# UFBmod_1V0.net
KiCad netlist of a schematic drawn in EAGLE
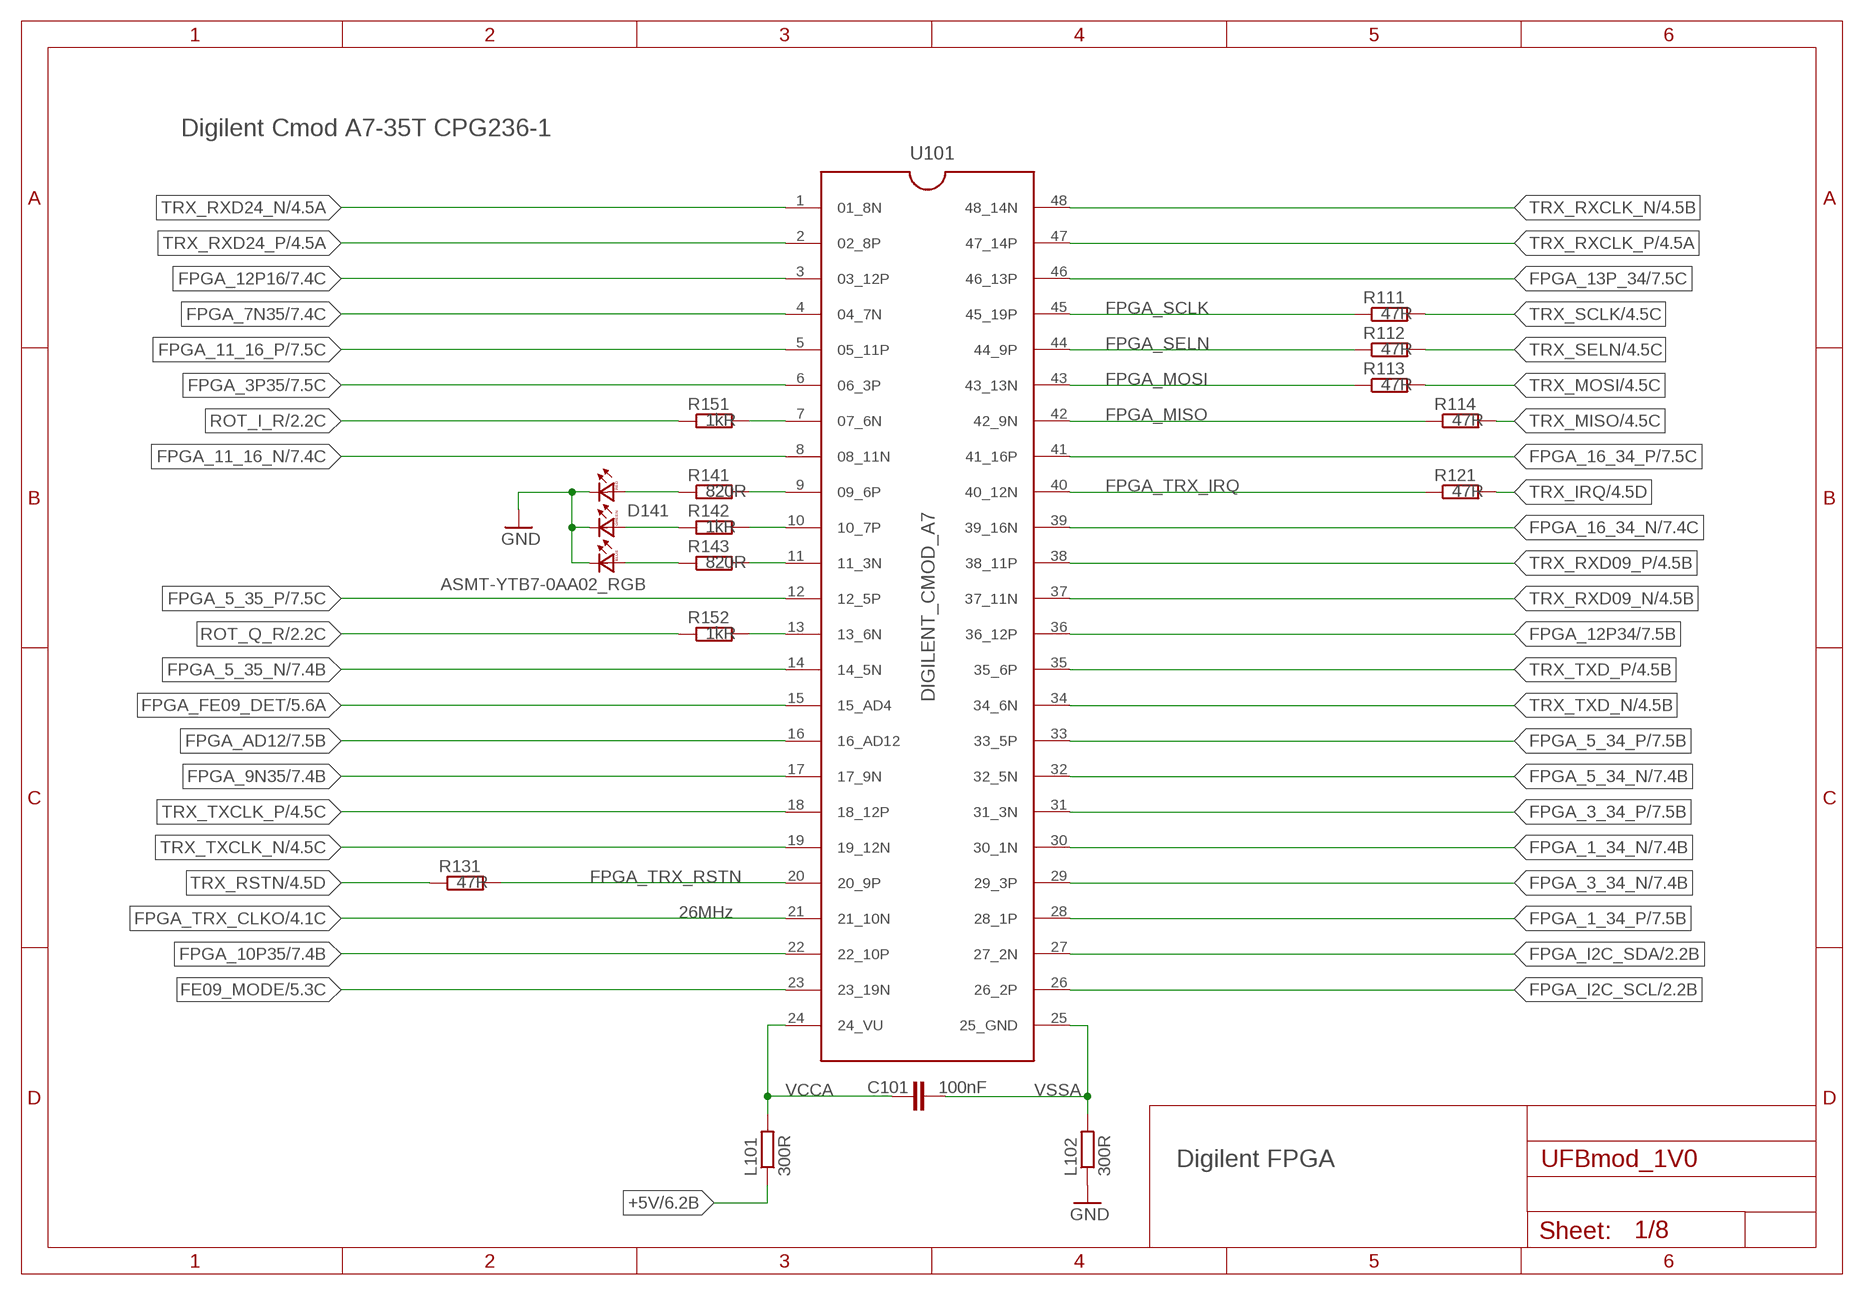
[diagram p0: schematic, sheet 1]
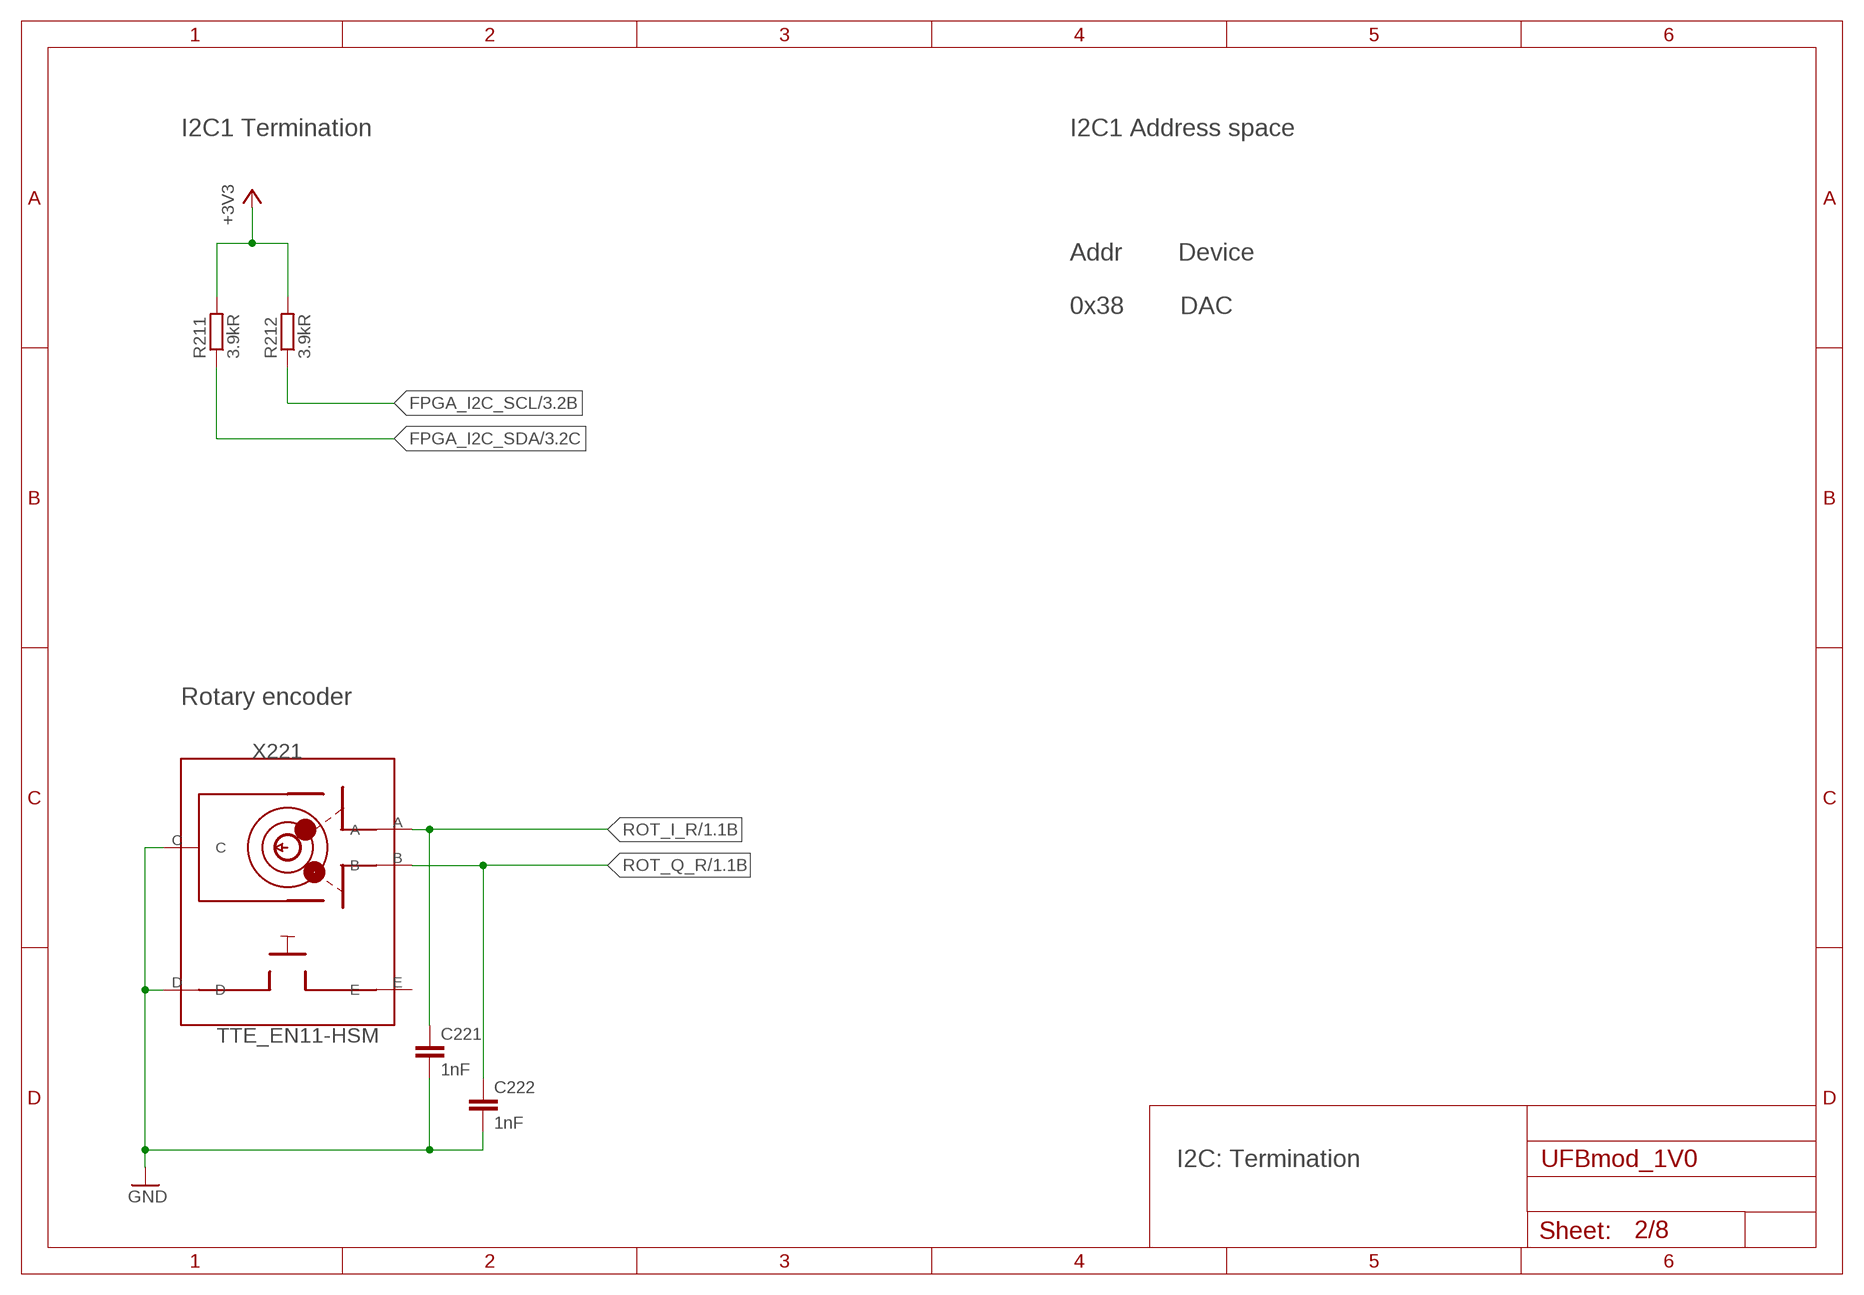
[diagram p1: schematic, sheet 2]
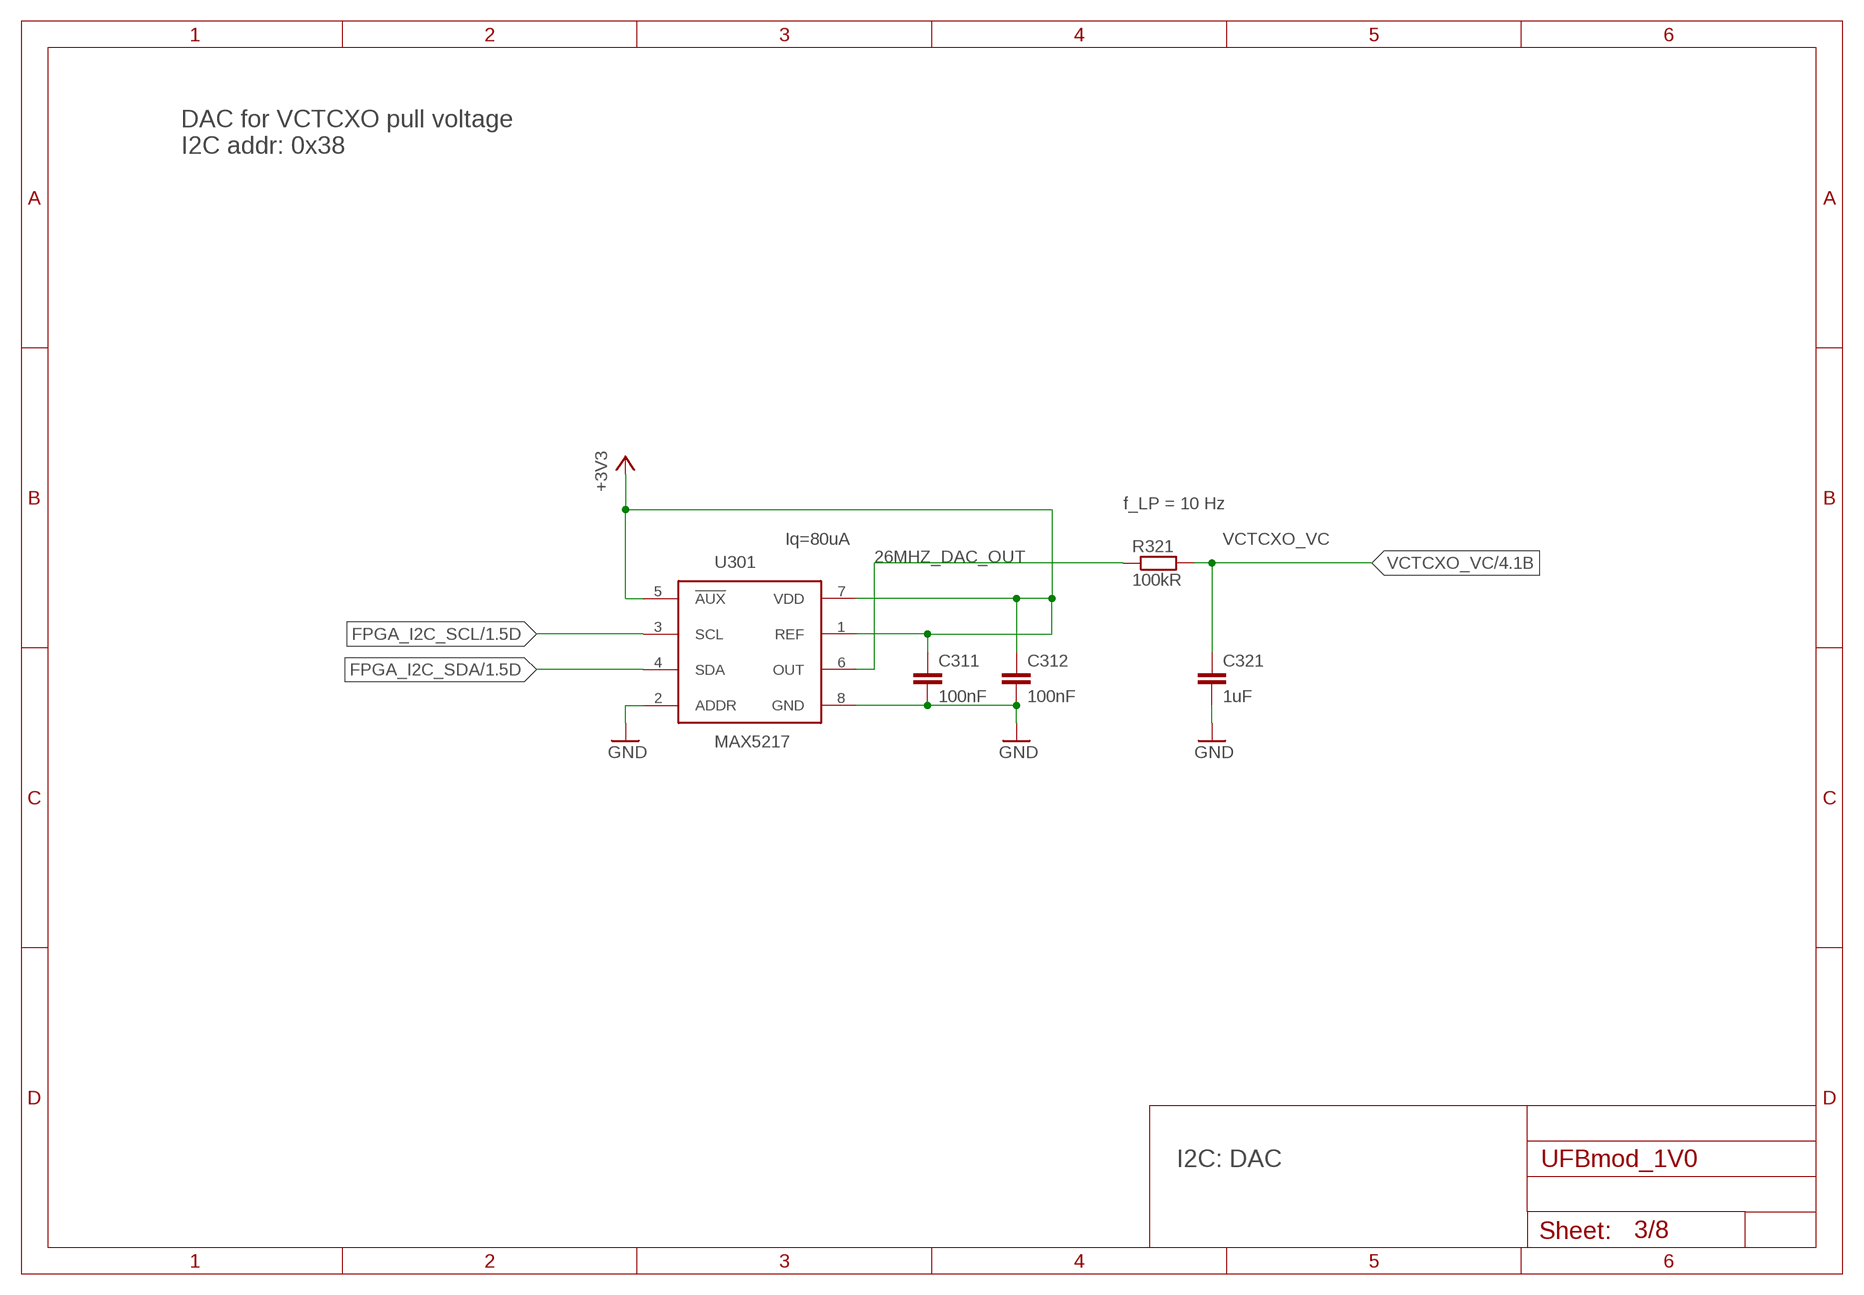
[diagram p2: schematic, sheet 3]
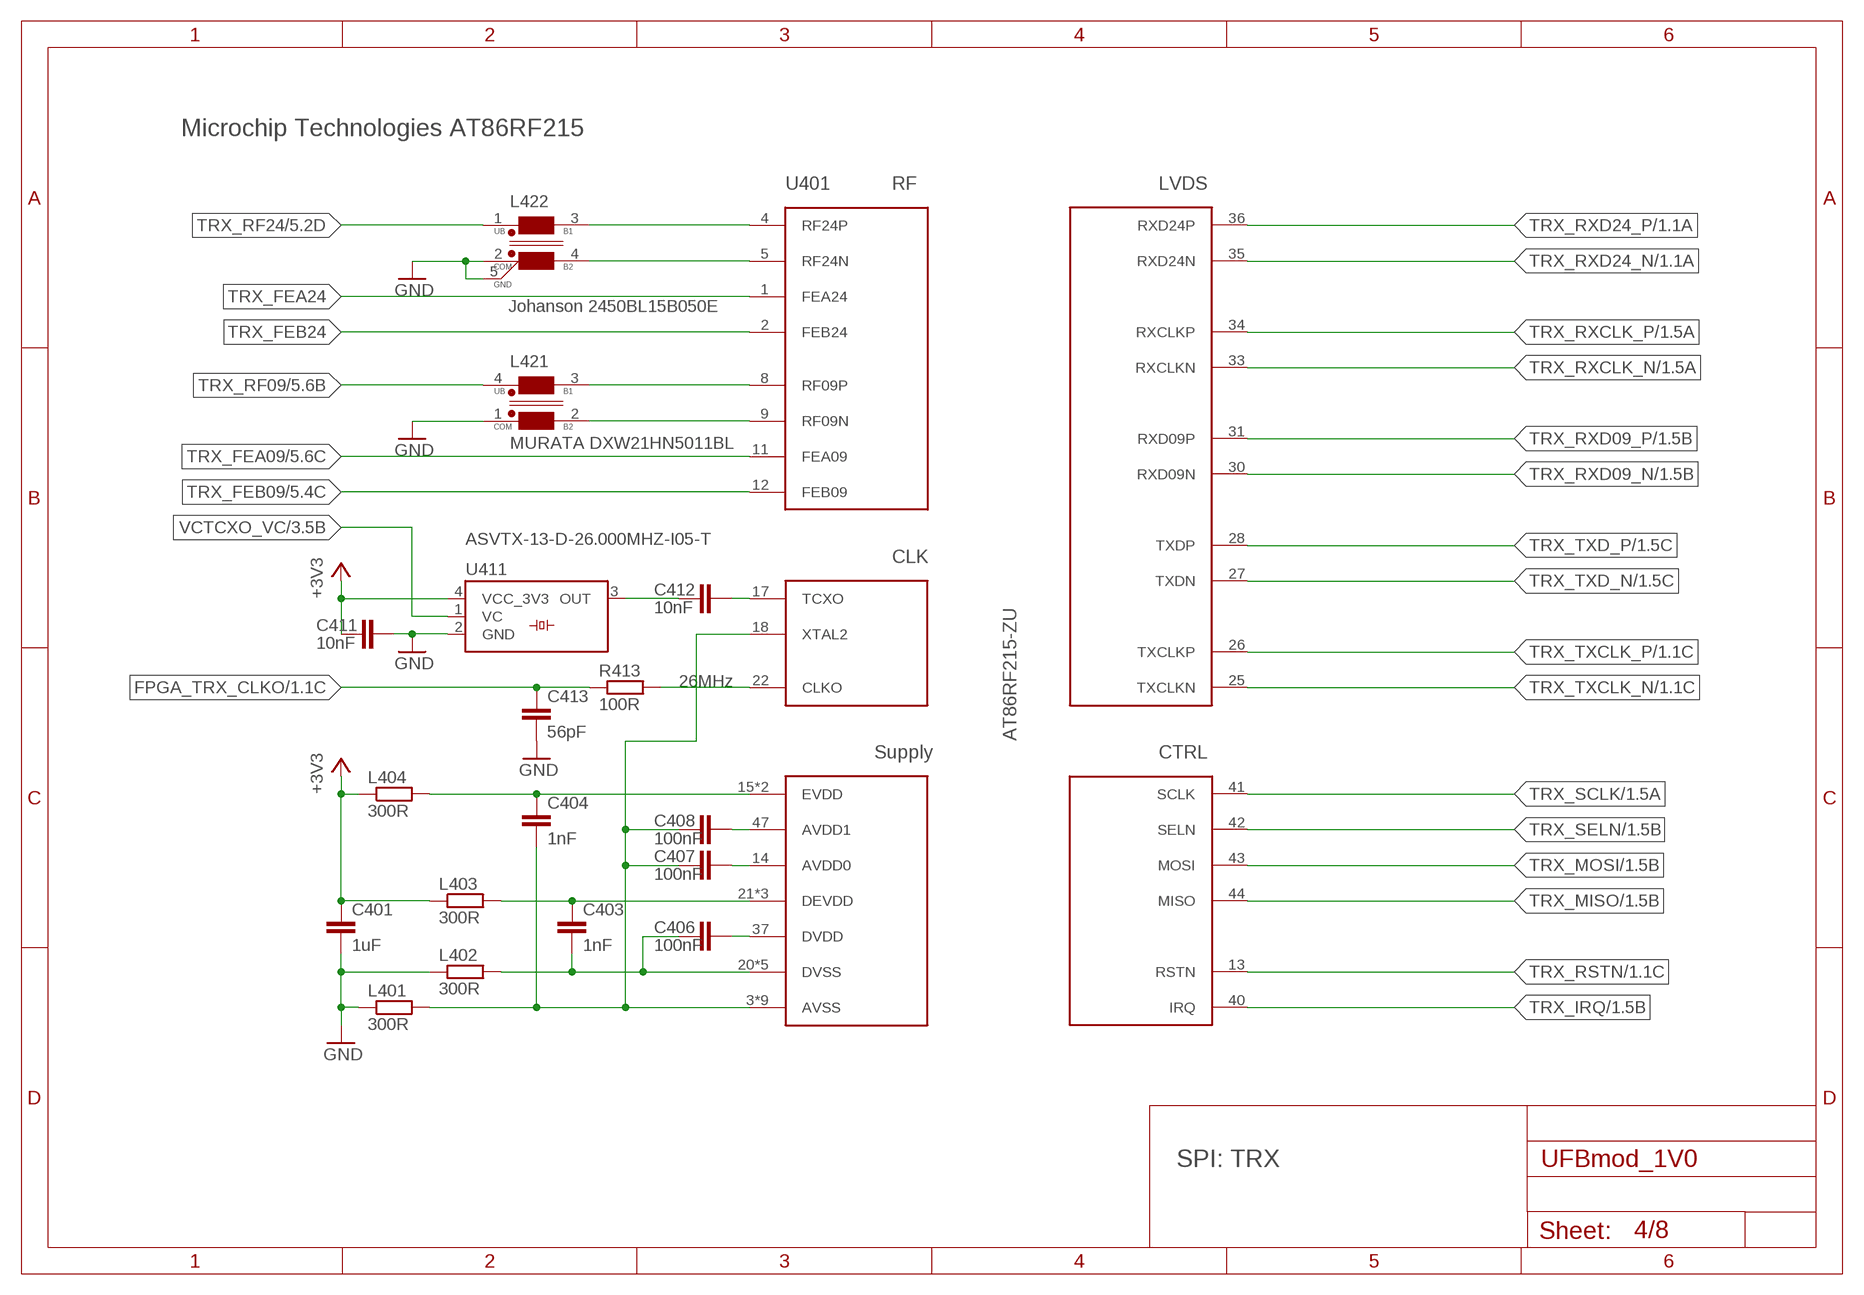
[diagram p3: schematic, sheet 4]
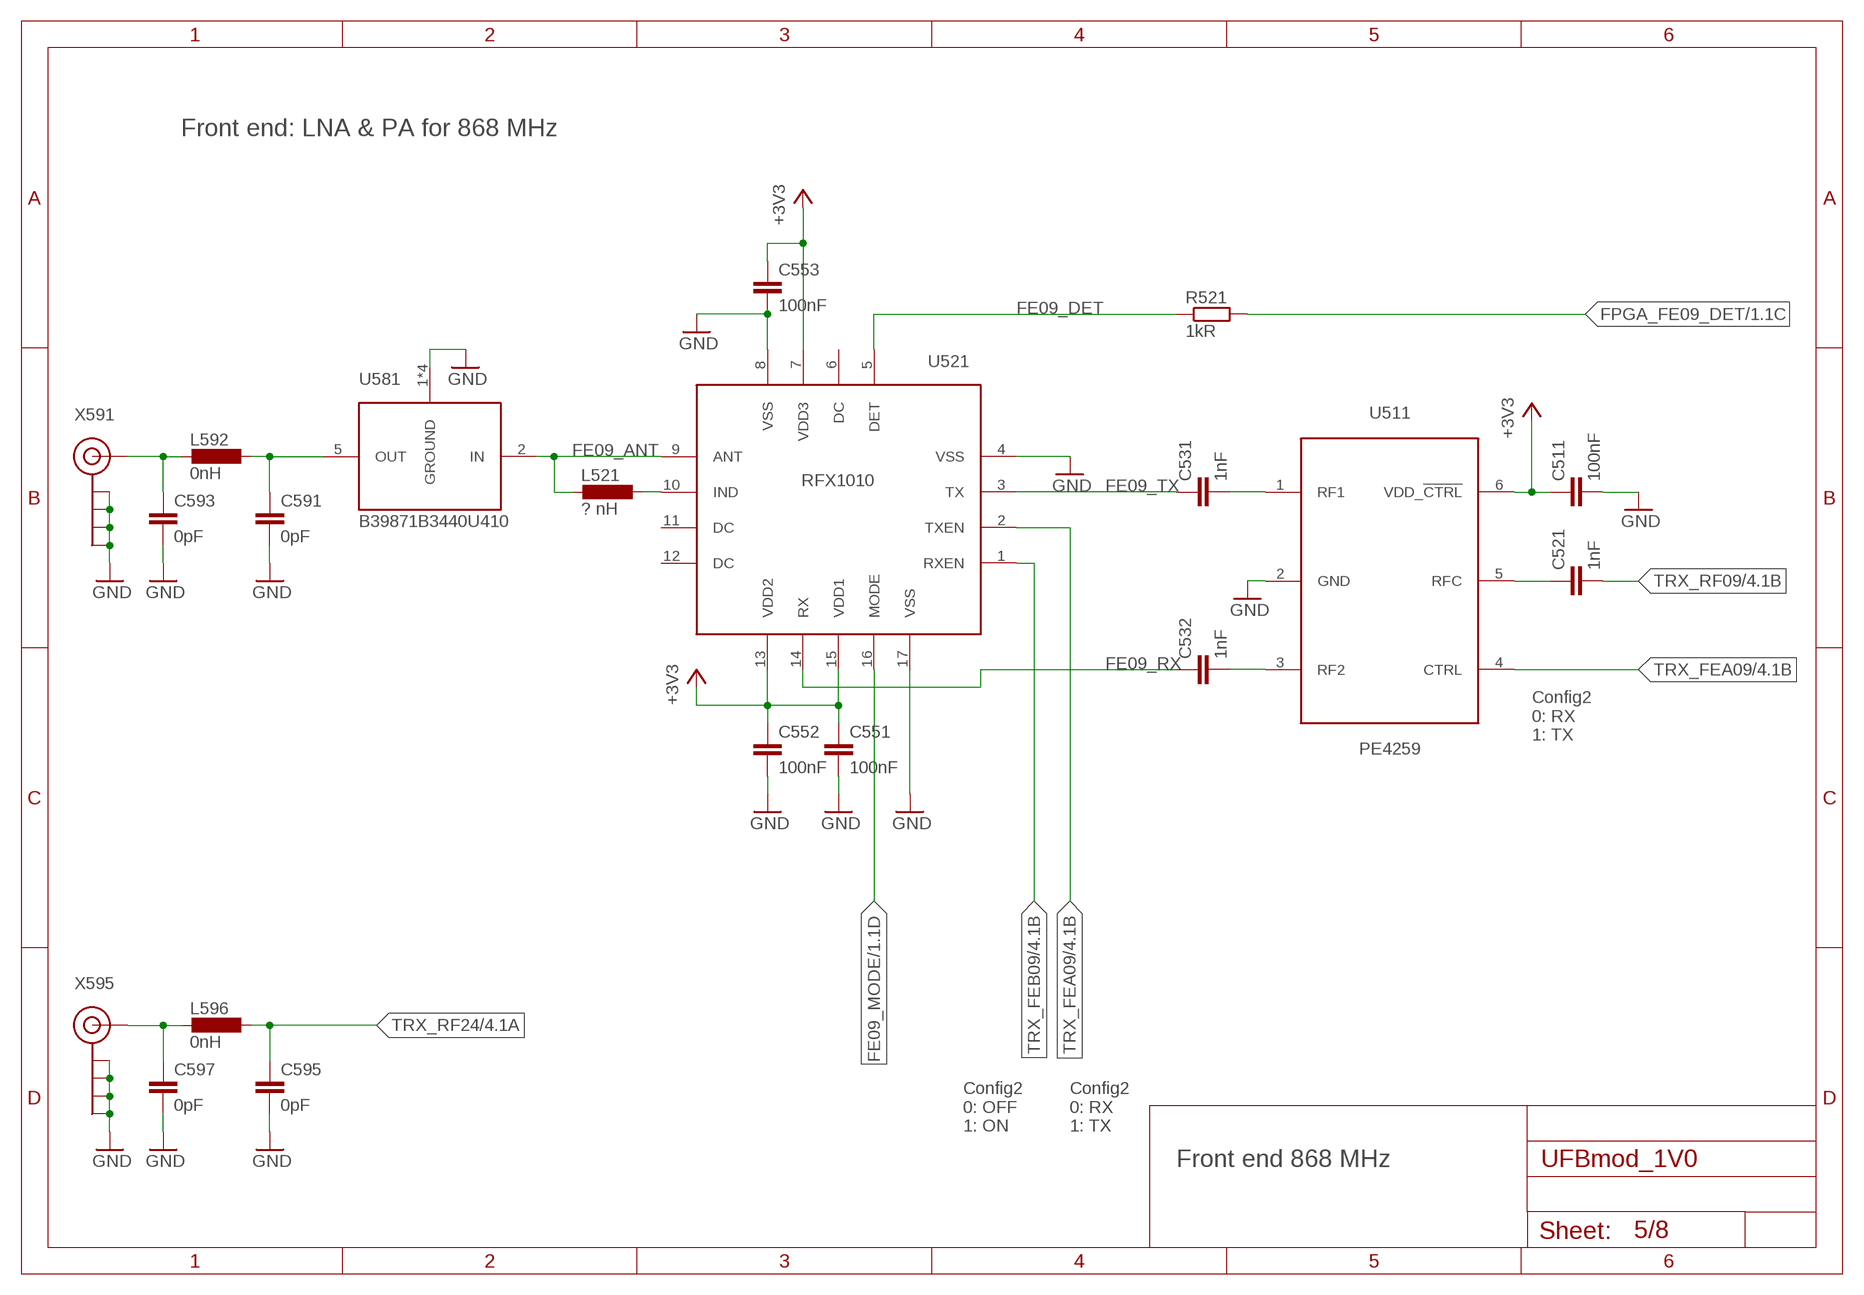
[diagram p4: schematic, sheet 5]
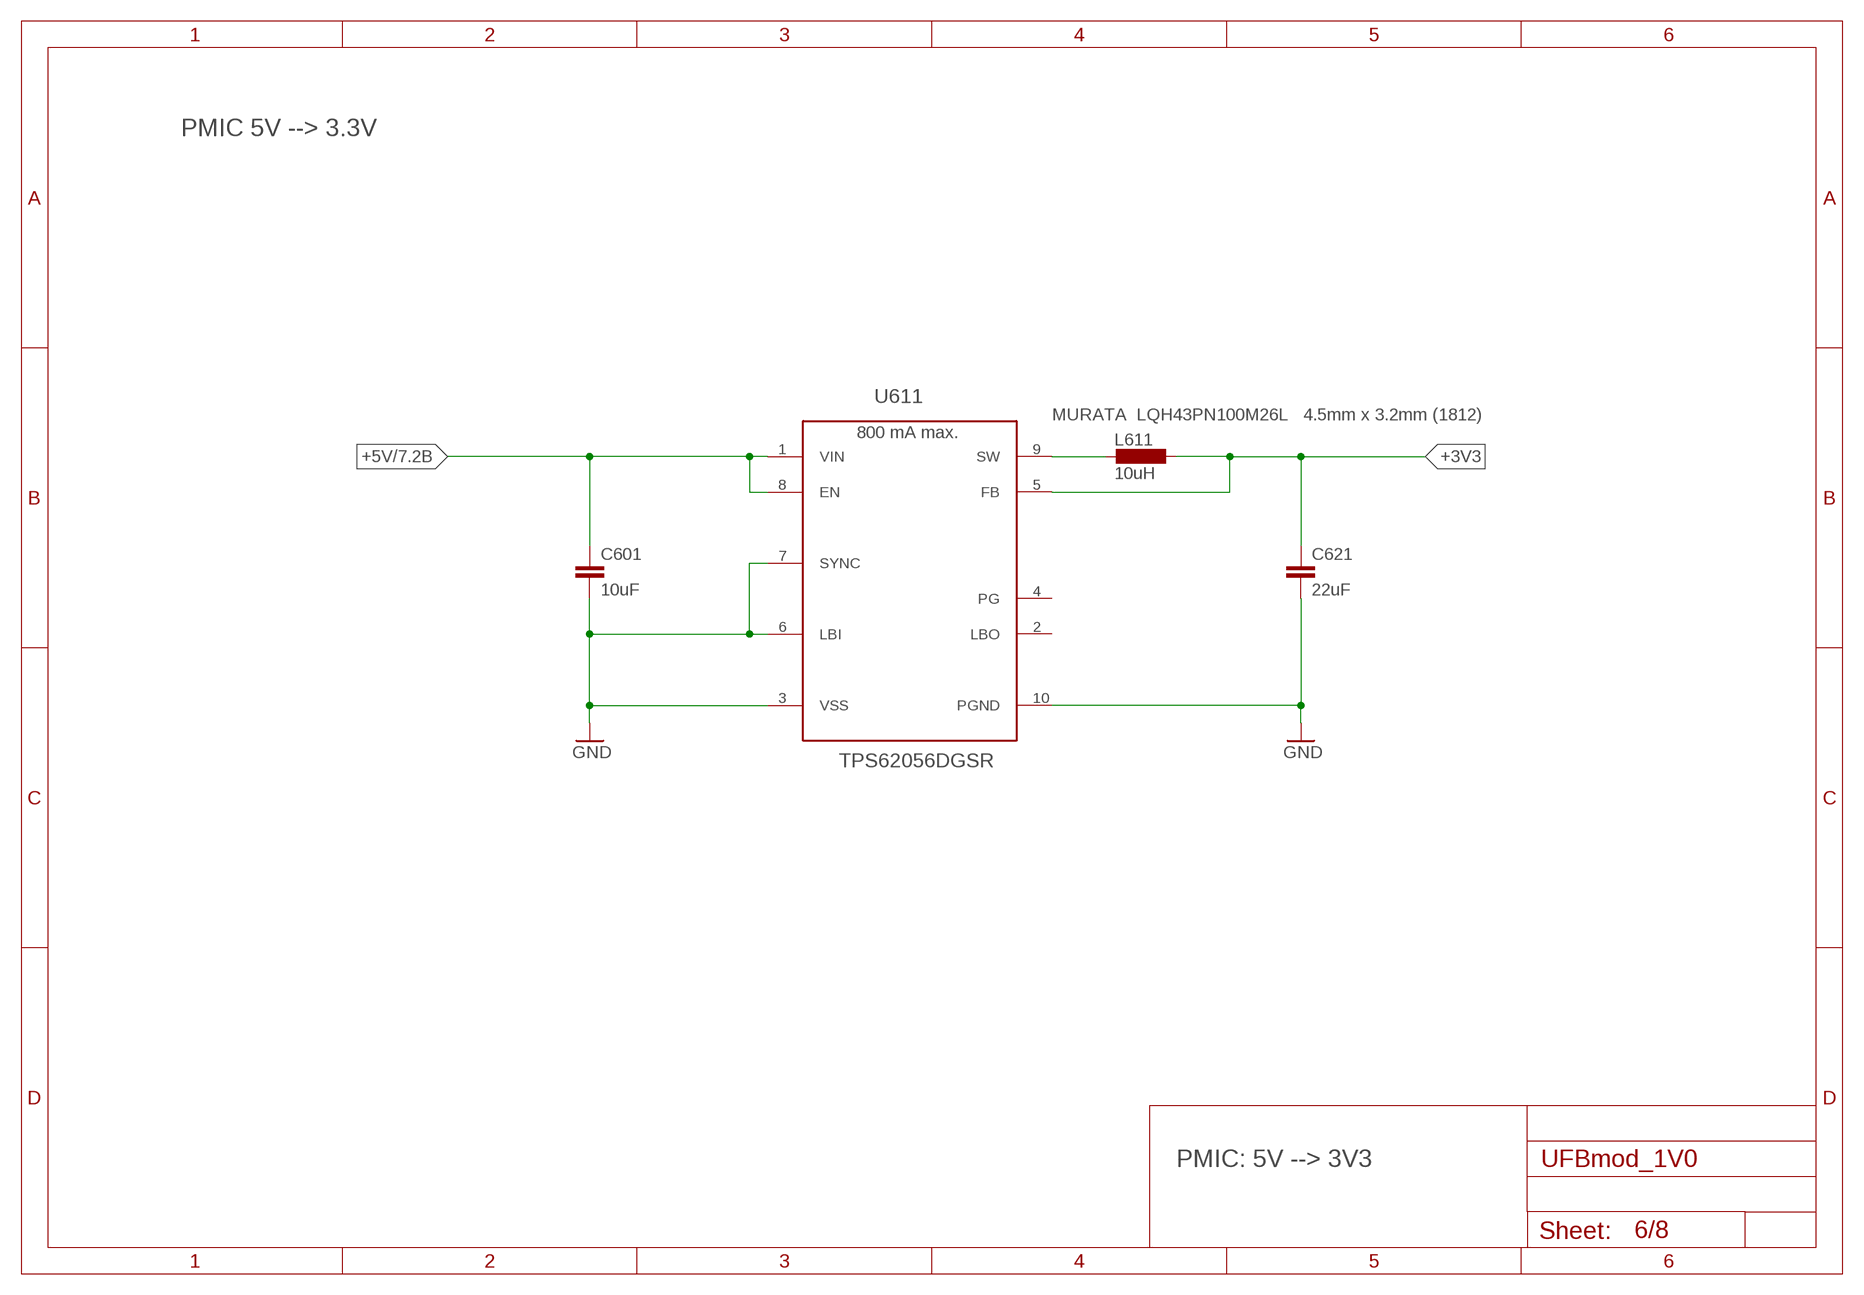
[diagram p5: schematic, sheet 6]
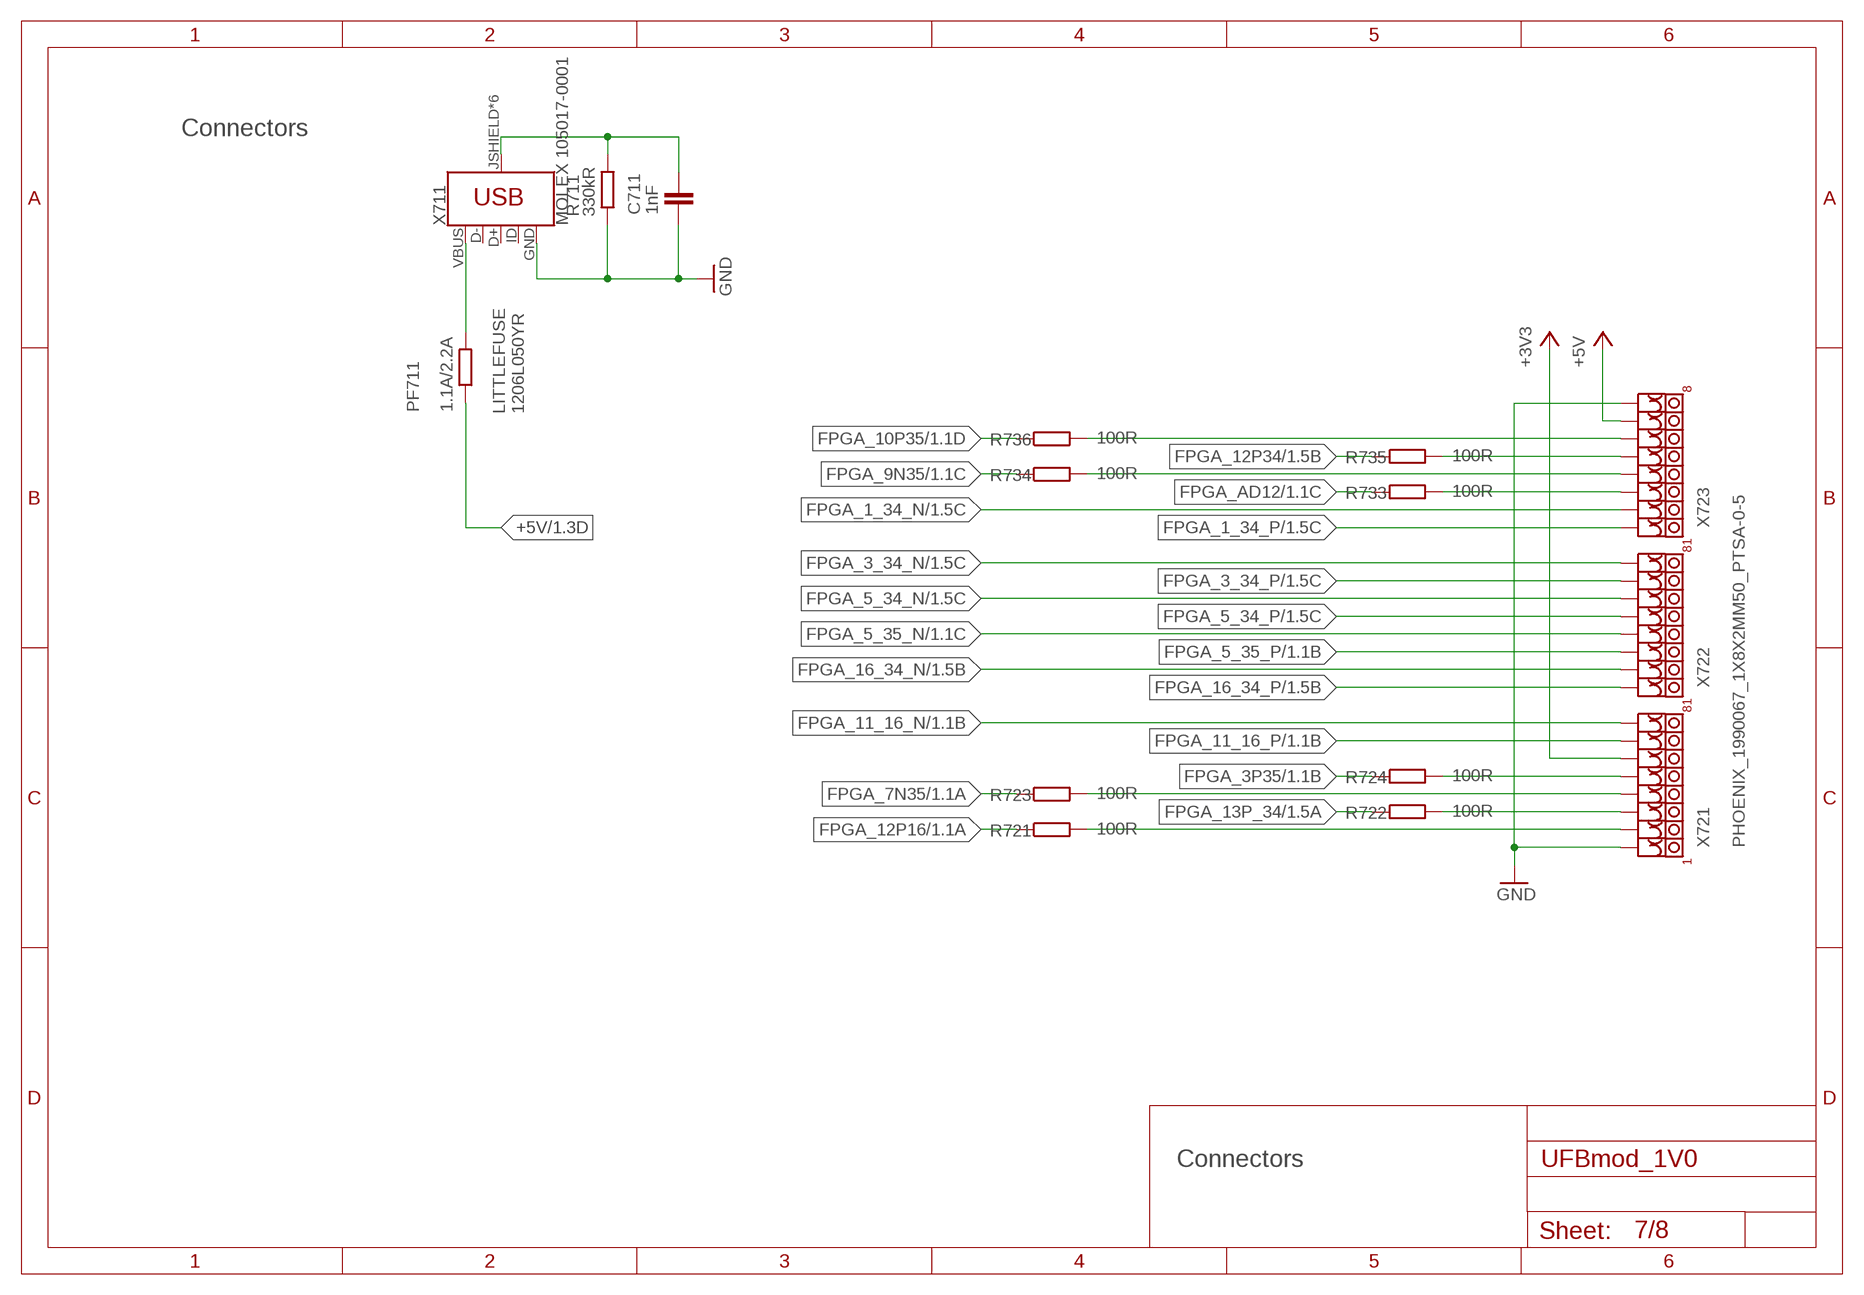
[diagram p6: schematic, sheet 7]
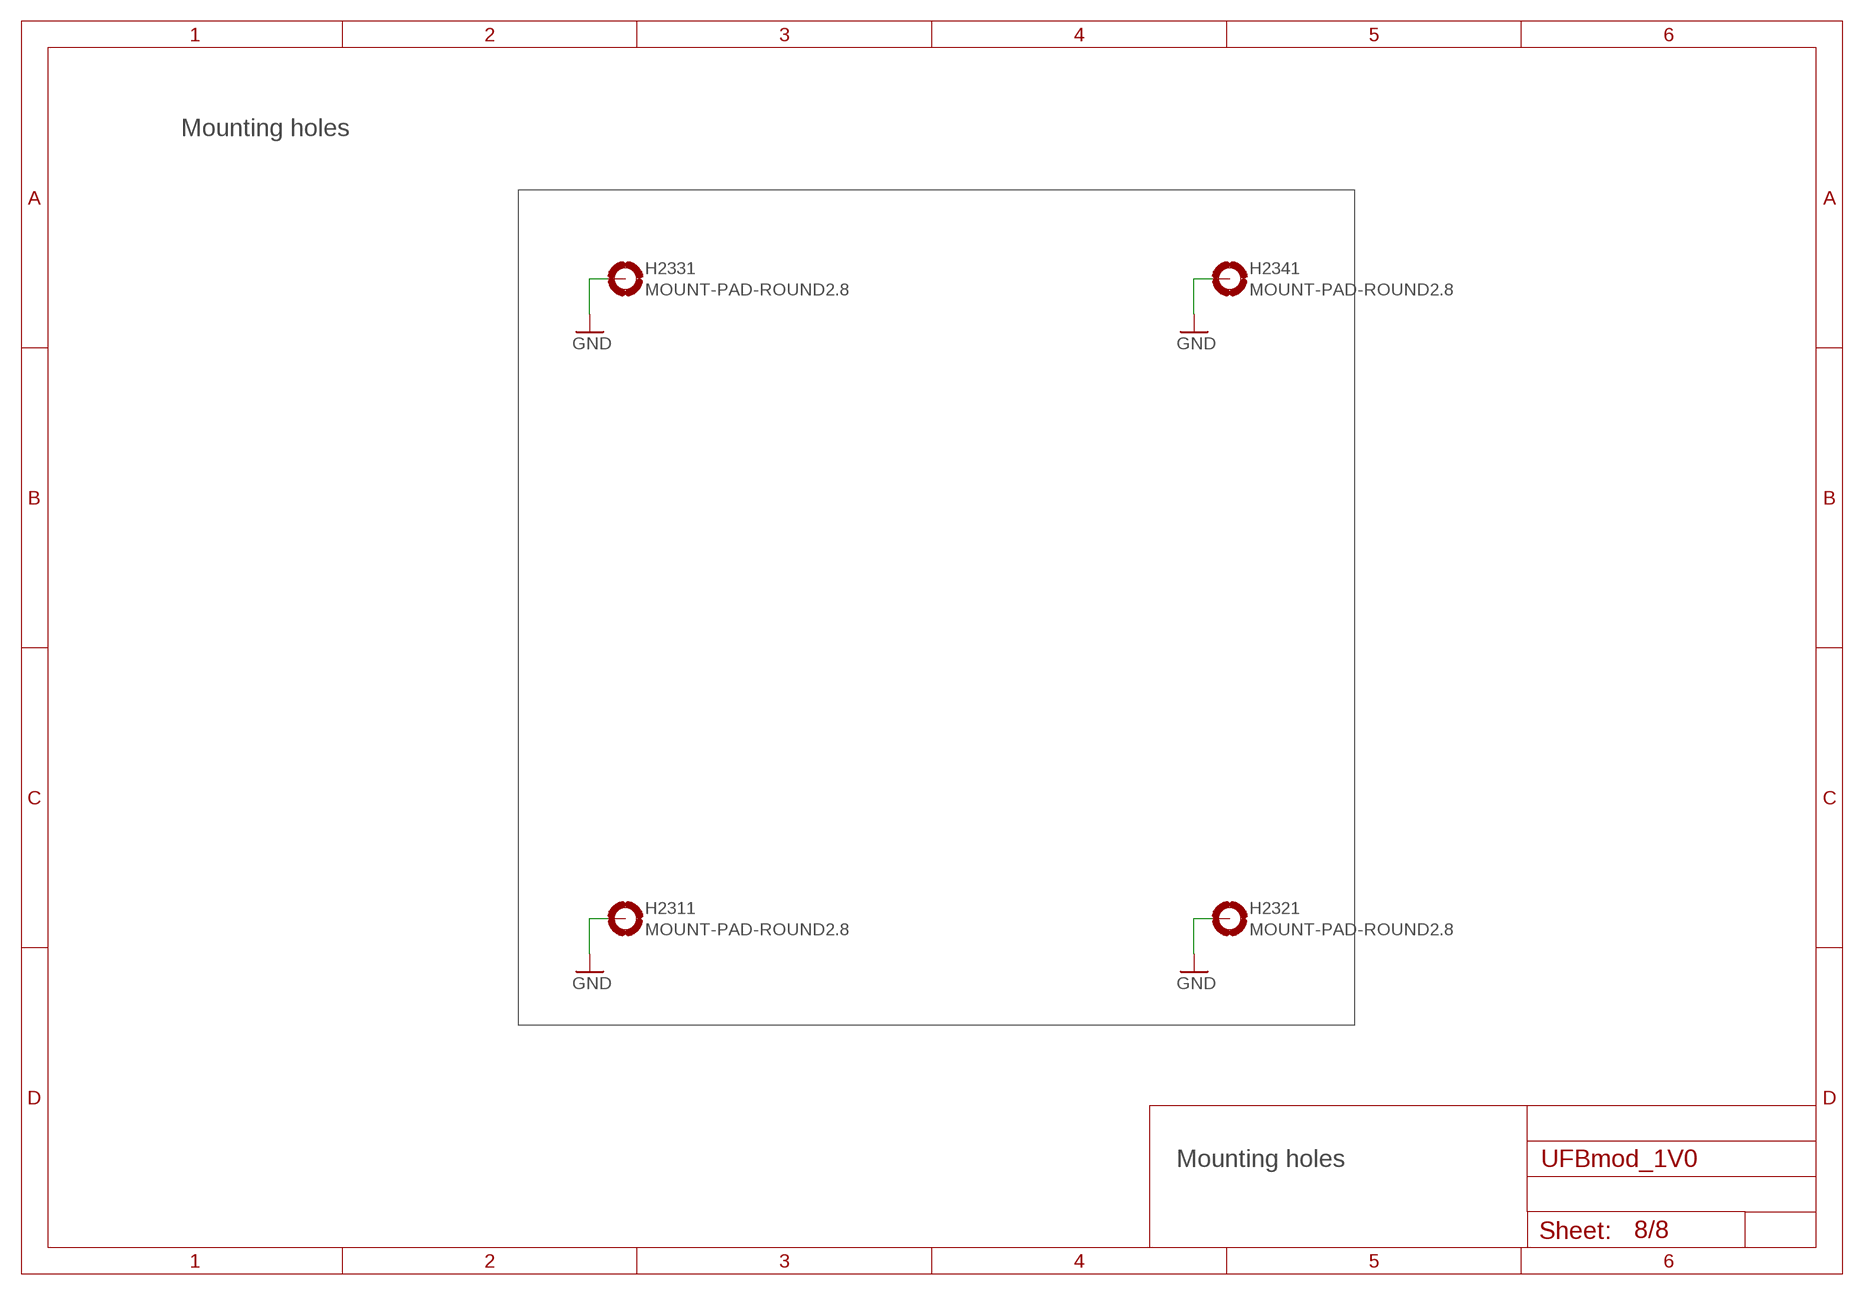
[diagram p7: schematic, sheet 8]

(export (version "E")
  (design (tool "Eeschema 10.0.6"))
  (components
    (comp (ref "C711")
      (value "1nF")
      (footprint "eagle-import:C0402")
      (libsource (lib "eagle-import") (part "C-EUC0402"))
    )
    (comp (ref "PF711")
      (value "1.1A/2.2A")
      (footprint "eagle-import:M1206")
      (libsource (lib "eagle-import") (part "rcl_R-EU_M1206"))
    )
    (comp (ref "R711")
      (value "330kR")
      (footprint "eagle-import:R0402")
      (libsource (lib "eagle-import") (part "R-EU_R0402"))
    )
    (comp (ref "R721")
      (value "100R")
      (footprint "eagle-import:R0402")
      (libsource (lib "eagle-import") (part "R-EU_R0402"))
    )
    (comp (ref "R722")
      (value "100R")
      (footprint "eagle-import:R0402")
      (libsource (lib "eagle-import") (part "R-EU_R0402"))
    )
    (comp (ref "R723")
      (value "100R")
      (footprint "eagle-import:R0402")
      (libsource (lib "eagle-import") (part "R-EU_R0402"))
    )
    (comp (ref "R724")
      (value "100R")
      (footprint "eagle-import:R0402")
      (libsource (lib "eagle-import") (part "R-EU_R0402"))
    )
    (comp (ref "R733")
      (value "100R")
      (footprint "eagle-import:R0402")
      (libsource (lib "eagle-import") (part "R-EU_R0402"))
    )
    (comp (ref "R734")
      (value "100R")
      (footprint "eagle-import:R0402")
      (libsource (lib "eagle-import") (part "R-EU_R0402"))
    )
    (comp (ref "R735")
      (value "100R")
      (footprint "eagle-import:R0402")
      (libsource (lib "eagle-import") (part "R-EU_R0402"))
    )
    (comp (ref "R736")
      (value "100R")
      (footprint "eagle-import:R0402")
      (libsource (lib "eagle-import") (part "R-EU_R0402"))
    )
    (comp (ref "X711")
      (value "MOLEX 105017-0001")
      (footprint "eagle-import:USB-B-MICRO-SMD_MOLEX-105017-0001")
      (libsource (lib "eagle-import") (part "USB_MICRO-B_MOLEX"))
    )
    (comp (ref "X721")
      (value "PHOENIX_1990067_1X8X2MM50_PTSA-0-5")
      (footprint "eagle-import:PHOENIX_1990067_1X8X2MM50_PTSA-0-5")
      (libsource (lib "eagle-import") (part "PHOENIX_1990067_1X8X2MM50_PTSA-0-5"))
    )
    (comp (ref "X722")
      (value "PHOENIX_1990067_1X8X2MM50_PTSA-0-5")
      (footprint "eagle-import:PHOENIX_1990067_1X8X2MM50_PTSA-0-5")
      (libsource (lib "eagle-import") (part "PHOENIX_1990067_1X8X2MM50_PTSA-0-5"))
    )
    (comp (ref "X723")
      (value "PHOENIX_1990067_1X8X2MM50_PTSA-0-5")
      (footprint "eagle-import:PHOENIX_1990067_1X8X2MM50_PTSA-0-5")
      (libsource (lib "eagle-import") (part "PHOENIX_1990067_1X8X2MM50_PTSA-0-5"))
    )
    (comp (ref "C311")
      (value "100nF")
      (footprint "eagle-import:C0402")
      (libsource (lib "eagle-import") (part "C-EUC0402"))
    )
    (comp (ref "C312")
      (value "100nF")
      (footprint "eagle-import:C0402")
      (libsource (lib "eagle-import") (part "C-EUC0402"))
    )
    (comp (ref "C321")
      (value "1uF")
      (footprint "eagle-import:C0402")
      (libsource (lib "eagle-import") (part "C-EUC0402"))
    )
    (comp (ref "R321")
      (value "100kR")
      (footprint "eagle-import:R0402")
      (libsource (lib "eagle-import") (part "R-EU_R0402"))
    )
    (comp (ref "U301")
      (value "MAX5217")
      (footprint "eagle-import:µMAX8")
      (libsource (lib "eagle-import") (part "MAX5217"))
    )
    (comp (ref "C601")
      (value "10uF")
      (footprint "eagle-import:C0603")
      (libsource (lib "eagle-import") (part "C-EUC0603"))
    )
    (comp (ref "C621")
      (value "22uF")
      (footprint "eagle-import:C0603")
      (libsource (lib "eagle-import") (part "C-EUC0603"))
    )
    (comp (ref "L611")
      (value "10uH")
      (footprint "eagle-import:L1812")
      (libsource (lib "eagle-import") (part "L-EUL1812"))
    )
    (comp (ref "U611")
      (value "TPS62056DGSR")
      (footprint "eagle-import:S-PDSO-G10")
      (libsource (lib "eagle-import") (part "TPS62051"))
    )
    (comp (ref "C221")
      (value "1nF")
      (footprint "eagle-import:C0402")
      (libsource (lib "eagle-import") (part "C-EUC0402"))
    )
    (comp (ref "C222")
      (value "1nF")
      (footprint "eagle-import:C0402")
      (libsource (lib "eagle-import") (part "C-EUC0402"))
    )
    (comp (ref "R211")
      (value "3.9kR")
      (footprint "eagle-import:R0402")
      (libsource (lib "eagle-import") (part "R-EU_R0402"))
    )
    (comp (ref "R212")
      (value "3.9kR")
      (footprint "eagle-import:R0402")
      (libsource (lib "eagle-import") (part "R-EU_R0402"))
    )
    (comp (ref "X221")
      (value "TTE_EN11-HSM")
      (footprint "eagle-import:TTE_EN11-HSM")
      (libsource (lib "eagle-import") (part "TTE_EN11-HSM"))
    )
    (comp (ref "H2311")
      (value "MOUNT-PAD-ROUND2.8")
      (footprint "eagle-import:2,8-PAD")
      (libsource (lib "eagle-import") (part "MOUNT-PAD-ROUND2.8"))
    )
    (comp (ref "H2321")
      (value "MOUNT-PAD-ROUND2.8")
      (footprint "eagle-import:2,8-PAD")
      (libsource (lib "eagle-import") (part "MOUNT-PAD-ROUND2.8"))
    )
    (comp (ref "H2331")
      (value "MOUNT-PAD-ROUND2.8")
      (footprint "eagle-import:2,8-PAD")
      (libsource (lib "eagle-import") (part "MOUNT-PAD-ROUND2.8"))
    )
    (comp (ref "H2341")
      (value "MOUNT-PAD-ROUND2.8")
      (footprint "eagle-import:2,8-PAD")
      (libsource (lib "eagle-import") (part "MOUNT-PAD-ROUND2.8"))
    )
    (comp (ref "C511")
      (value "100nF")
      (footprint "eagle-import:C0402")
      (libsource (lib "eagle-import") (part "C-EUC0402"))
    )
    (comp (ref "C521")
      (value "1nF")
      (footprint "eagle-import:C0402")
      (libsource (lib "eagle-import") (part "C-EUC0402"))
    )
    (comp (ref "C531")
      (value "1nF")
      (footprint "eagle-import:C0402")
      (libsource (lib "eagle-import") (part "C-EUC0402"))
    )
    (comp (ref "C532")
      (value "1nF")
      (footprint "eagle-import:C0402")
      (libsource (lib "eagle-import") (part "C-EUC0402"))
    )
    (comp (ref "C551")
      (value "100nF")
      (footprint "eagle-import:C0402")
      (libsource (lib "eagle-import") (part "C-EUC0402"))
    )
    (comp (ref "C552")
      (value "100nF")
      (footprint "eagle-import:C0402")
      (libsource (lib "eagle-import") (part "C-EUC0402"))
    )
    (comp (ref "C553")
      (value "100nF")
      (footprint "eagle-import:C0402")
      (libsource (lib "eagle-import") (part "C-EUC0402"))
    )
    (comp (ref "C591")
      (value "0pF")
      (footprint "eagle-import:C0402")
      (libsource (lib "eagle-import") (part "C-EUC0402"))
    )
    (comp (ref "C593")
      (value "0pF")
      (footprint "eagle-import:C0402")
      (libsource (lib "eagle-import") (part "C-EUC0402"))
    )
    (comp (ref "C595")
      (value "0pF")
      (footprint "eagle-import:C0402")
      (libsource (lib "eagle-import") (part "C-EUC0402"))
    )
    (comp (ref "C597")
      (value "0pF")
      (footprint "eagle-import:C0402")
      (libsource (lib "eagle-import") (part "C-EUC0402"))
    )
    (comp (ref "L521")
      (value "? nH")
      (footprint "eagle-import:L0603")
      (libsource (lib "eagle-import") (part "L-EUL0603"))
    )
    (comp (ref "L592")
      (value "0nH")
      (footprint "eagle-import:L0603")
      (libsource (lib "eagle-import") (part "L-EUL0603"))
    )
    (comp (ref "L596")
      (value "0nH")
      (footprint "eagle-import:L0603")
      (libsource (lib "eagle-import") (part "L-EUL0603"))
    )
    (comp (ref "R521")
      (value "1kR")
      (footprint "eagle-import:R0402")
      (libsource (lib "eagle-import") (part "R-EU_R0402"))
    )
    (comp (ref "U511")
      (value "PE4259")
      (footprint "eagle-import:SC-70_6-LEAD_2X1MM25_0P65")
      (libsource (lib "eagle-import") (part "PE4259"))
    )
    (comp (ref "U521")
      (value "RFX1010")
      (footprint "eagle-import:QFN16-3X3-0P5-PAD")
      (libsource (lib "eagle-import") (part "RFX1010"))
    )
    (comp (ref "U581")
      (value "B39871B3440U410")
      (footprint "eagle-import:B3440_3MM-X-3MM")
      (libsource (lib "eagle-import") (part "B3440"))
    )
    (comp (ref "X591")
      (value "ANTENNATINY")
      (footprint "eagle-import:SMA_UFL_PAD_TINY")
      (libsource (lib "eagle-import") (part "ANTENNATINY"))
    )
    (comp (ref "X595")
      (value "ANTENNATINY")
      (footprint "eagle-import:SMA_UFL_PAD_TINY")
      (libsource (lib "eagle-import") (part "ANTENNATINY"))
    )
    (comp (ref "C101")
      (value "100nF")
      (footprint "eagle-import:C0402")
      (libsource (lib "eagle-import") (part "C-EUC0402"))
    )
    (comp (ref "D141")
      (value "ASMT-YTB7-0AA02_RGB")
      (footprint "eagle-import:ASMT-YTB7_0AA02_RGB")
      (libsource (lib "eagle-import") (part "ASMT-YTB7-0AA02_RGB"))
    )
    (comp (ref "L101")
      (value "300R")
      (footprint "eagle-import:R1206")
      (libsource (lib "eagle-import") (part "R-EU_R1206"))
    )
    (comp (ref "L102")
      (value "300R")
      (footprint "eagle-import:R1206")
      (libsource (lib "eagle-import") (part "R-EU_R1206"))
    )
    (comp (ref "R111")
      (value "47R")
      (footprint "eagle-import:R0402")
      (libsource (lib "eagle-import") (part "R-EU_R0402"))
    )
    (comp (ref "R112")
      (value "47R")
      (footprint "eagle-import:R0402")
      (libsource (lib "eagle-import") (part "R-EU_R0402"))
    )
    (comp (ref "R113")
      (value "47R")
      (footprint "eagle-import:R0402")
      (libsource (lib "eagle-import") (part "R-EU_R0402"))
    )
    (comp (ref "R114")
      (value "47R")
      (footprint "eagle-import:R0402")
      (libsource (lib "eagle-import") (part "R-EU_R0402"))
    )
    (comp (ref "R121")
      (value "47R")
      (footprint "eagle-import:R0402")
      (libsource (lib "eagle-import") (part "R-EU_R0402"))
    )
    (comp (ref "R131")
      (value "47R")
      (footprint "eagle-import:R0402")
      (libsource (lib "eagle-import") (part "R-EU_R0402"))
    )
    (comp (ref "R141")
      (value "820R")
      (footprint "eagle-import:R0402")
      (libsource (lib "eagle-import") (part "R-EU_R0402"))
    )
    (comp (ref "R142")
      (value "1kR")
      (footprint "eagle-import:R0402")
      (libsource (lib "eagle-import") (part "R-EU_R0402"))
    )
    (comp (ref "R143")
      (value "820R")
      (footprint "eagle-import:R0402")
      (libsource (lib "eagle-import") (part "R-EU_R0402"))
    )
    (comp (ref "R151")
      (value "1kR")
      (footprint "eagle-import:R0402")
      (libsource (lib "eagle-import") (part "R-EU_R0402"))
    )
    (comp (ref "R152")
      (value "1kR")
      (footprint "eagle-import:R0402")
      (libsource (lib "eagle-import") (part "R-EU_R0402"))
    )
    (comp (ref "U101")
      (value "DIGILENT_CMOD_A7")
      (footprint "eagle-import:DIGILENT_CMOD_A7__DIP48")
      (libsource (lib "eagle-import") (part "DIGILENT_CMOD_A7"))
    )
    (comp (ref "C401")
      (value "1uF")
      (footprint "eagle-import:C0402")
      (libsource (lib "eagle-import") (part "C-EUC0402"))
    )
    (comp (ref "C403")
      (value "1nF")
      (footprint "eagle-import:C0402")
      (libsource (lib "eagle-import") (part "C-EUC0402"))
    )
    (comp (ref "C404")
      (value "1nF")
      (footprint "eagle-import:C0402")
      (libsource (lib "eagle-import") (part "C-EUC0402"))
    )
    (comp (ref "C406")
      (value "100nF")
      (footprint "eagle-import:C0402")
      (libsource (lib "eagle-import") (part "C-EUC0402"))
    )
    (comp (ref "C407")
      (value "100nF")
      (footprint "eagle-import:C0402")
      (libsource (lib "eagle-import") (part "C-EUC0402"))
    )
    (comp (ref "C408")
      (value "100nF")
      (footprint "eagle-import:C0402")
      (libsource (lib "eagle-import") (part "C-EUC0402"))
    )
    (comp (ref "C411")
      (value "10nF")
      (footprint "eagle-import:C0402")
      (libsource (lib "eagle-import") (part "C-EUC0402"))
    )
    (comp (ref "C412")
      (value "10nF")
      (footprint "eagle-import:C0402")
      (libsource (lib "eagle-import") (part "C-EUC0402"))
    )
    (comp (ref "C413")
      (value "56pF")
      (footprint "eagle-import:C0402")
      (libsource (lib "eagle-import") (part "C-EUC0402"))
    )
    (comp (ref "L401")
      (value "300R")
      (footprint "eagle-import:R1206")
      (libsource (lib "eagle-import") (part "R-EU_R1206"))
    )
    (comp (ref "L402")
      (value "300R")
      (footprint "eagle-import:R1206")
      (libsource (lib "eagle-import") (part "R-EU_R1206"))
    )
    (comp (ref "L403")
      (value "300R")
      (footprint "eagle-import:R1206")
      (libsource (lib "eagle-import") (part "R-EU_R1206"))
    )
    (comp (ref "L404")
      (value "300R")
      (footprint "eagle-import:R1206")
      (libsource (lib "eagle-import") (part "R-EU_R1206"))
    )
    (comp (ref "L421")
      (value "MURATA DXW21HN5011BL")
      (footprint "eagle-import:DXW21HN5011BL")
      (libsource (lib "eagle-import") (part "DXW21HN5011BL"))
    )
    (comp (ref "L422")
      (value "Johanson 2450BL15B050E")
      (footprint "eagle-import:2450BL15B050")
      (libsource (lib "eagle-import") (part "2450BL15B050"))
    )
    (comp (ref "R413")
      (value "100R")
      (footprint "eagle-import:R0402")
      (libsource (lib "eagle-import") (part "R-EU_R0402"))
    )
    (comp (ref "U401")
      (value "AT86RF215-ZU")
      (footprint "eagle-import:QFN48_7X7-0P5-PAD")
      (libsource (lib "eagle-import") (part "AT86RF215"))
    )
    (comp (ref "U411")
      (value "ASVTX-13-D-26.000MHZ-I05-T")
      (footprint "eagle-import:ASVTX-13")
      (libsource (lib "eagle-import") (part "ASVTX-13-D"))
    )
  )
  (nets
    (net (code "1") (name "+3V3") (class "Default")
      (node (ref "C311") (pin "1") (pinfunction "1_1") (pintype "passive"))
      (node (ref "C312") (pin "1") (pinfunction "1_1") (pintype "passive"))
      (node (ref "C401") (pin "1") (pinfunction "1_1") (pintype "passive"))
      (node (ref "C411") (pin "1") (pinfunction "1_1") (pintype "passive"))
      (node (ref "C511") (pin "1") (pinfunction "1_1") (pintype "passive"))
      (node (ref "C551") (pin "1") (pinfunction "1_1") (pintype "passive"))
      (node (ref "C552") (pin "1") (pinfunction "1_1") (pintype "passive"))
      (node (ref "C553") (pin "1") (pinfunction "1_1") (pintype "passive"))
      (node (ref "C621") (pin "1") (pinfunction "1_1") (pintype "passive"))
      (node (ref "L403") (pin "1") (pinfunction "1_1") (pintype "passive"))
      (node (ref "L404") (pin "1") (pinfunction "1_1") (pintype "passive"))
      (node (ref "L611") (pin "1") (pinfunction "1_1") (pintype "passive"))
      (node (ref "R211") (pin "2") (pinfunction "2_2") (pintype "passive"))
      (node (ref "R212") (pin "2") (pinfunction "2_2") (pintype "passive"))
      (node (ref "U301") (pin "1") (pinfunction "REF_1") (pintype "passive"))
      (node (ref "U301") (pin "5") (pinfunction "~{AUX}_5") (pintype "input"))
      (node (ref "U301") (pin "7") (pinfunction "VDD_7") (pintype "power_in"))
      (node (ref "U411") (pin "4") (pinfunction "VCC_3V3_4") (pintype "power_in"))
      (node (ref "U511") (pin "6") (pinfunction "VDD_~{CTRL}_6") (pintype "passive"))
      (node (ref "U521") (pin "13") (pinfunction "VDD2_13") (pintype "power_in"))
      (node (ref "U521") (pin "15") (pinfunction "VDD1_15") (pintype "power_in"))
      (node (ref "U521") (pin "7") (pinfunction "VDD3_7") (pintype "power_in"))
      (node (ref "U611") (pin "5") (pinfunction "FB_5") (pintype "passive"))
      (node (ref "X721") (pin "6") (pinfunction "6_6") (pintype "passive"))
    )
    (net (code "2") (name "+5V") (class "Default")
      (node (ref "C601") (pin "1") (pinfunction "1_1") (pintype "passive"))
      (node (ref "L101") (pin "1") (pinfunction "1_1") (pintype "passive"))
      (node (ref "PF711") (pin "1") (pinfunction "1_1") (pintype "passive"))
      (node (ref "U611") (pin "1") (pinfunction "VIN_1") (pintype "power_in"))
      (node (ref "U611") (pin "8") (pinfunction "EN_8") (pintype "input"))
      (node (ref "X723") (pin "7") (pinfunction "7_7") (pintype "passive"))
    )
    (net (code "3") (name "26MHZ_DAC_OUT") (class "Default")
      (node (ref "R321") (pin "1") (pinfunction "1_1") (pintype "passive"))
      (node (ref "U301") (pin "6") (pinfunction "OUT_6") (pintype "passive"))
    )
    (net (code "4") (name "FE09_ANT") (class "Default")
      (node (ref "L521") (pin "2") (pinfunction "2_2") (pintype "passive"))
      (node (ref "U521") (pin "9") (pinfunction "ANT_9") (pintype "bidirectional"))
      (node (ref "U581") (pin "2") (pinfunction "IN_2") (pintype "passive"))
    )
    (net (code "5") (name "FE09_DET") (class "Default")
      (node (ref "R521") (pin "1") (pinfunction "1_1") (pintype "passive"))
      (node (ref "U521") (pin "5") (pinfunction "DET_5") (pintype "output"))
    )
    (net (code "6") (name "FE09_MODE") (class "Default")
      (node (ref "U101") (pin "23") (pinfunction "23_19N_23") (pintype "bidirectional"))
      (node (ref "U521") (pin "16") (pinfunction "MODE_16") (pintype "input"))
    )
    (net (code "7") (name "FE09_RX") (class "Default")
      (node (ref "C532") (pin "1") (pinfunction "1_1") (pintype "passive"))
      (node (ref "U521") (pin "14") (pinfunction "RX_14") (pintype "output"))
    )
    (net (code "8") (name "FE09_TX") (class "Default")
      (node (ref "C531") (pin "1") (pinfunction "1_1") (pintype "passive"))
      (node (ref "U521") (pin "3") (pinfunction "TX_3") (pintype "input"))
    )
    (net (code "9") (name "FPGA_1_34_N") (class "Default")
      (node (ref "U101") (pin "30") (pinfunction "30_1N_30") (pintype "bidirectional"))
      (node (ref "X723") (pin "2") (pinfunction "2_2") (pintype "passive"))
    )
    (net (code "10") (name "FPGA_1_34_P") (class "Default")
      (node (ref "U101") (pin "28") (pinfunction "28_1P_28") (pintype "bidirectional"))
      (node (ref "X723") (pin "1") (pinfunction "1_1") (pintype "passive"))
    )
    (net (code "11") (name "FPGA_3P35") (class "Default")
      (node (ref "R724") (pin "1") (pinfunction "1_1") (pintype "passive"))
      (node (ref "U101") (pin "6") (pinfunction "06_3P_6") (pintype "bidirectional"))
    )
    (net (code "12") (name "FPGA_3_34_N") (class "Default")
      (node (ref "U101") (pin "29") (pinfunction "29_3P_29") (pintype "bidirectional"))
      (node (ref "X722") (pin "8") (pinfunction "8_8") (pintype "passive"))
    )
    (net (code "13") (name "FPGA_3_34_P") (class "Default")
      (node (ref "U101") (pin "31") (pinfunction "31_3N_31") (pintype "bidirectional"))
      (node (ref "X722") (pin "7") (pinfunction "7_7") (pintype "passive"))
    )
    (net (code "14") (name "FPGA_5_34_N") (class "Default")
      (node (ref "U101") (pin "32") (pinfunction "32_5N_32") (pintype "bidirectional"))
      (node (ref "X722") (pin "6") (pinfunction "6_6") (pintype "passive"))
    )
    (net (code "15") (name "FPGA_5_34_P") (class "Default")
      (node (ref "U101") (pin "33") (pinfunction "33_5P_33") (pintype "bidirectional"))
      (node (ref "X722") (pin "5") (pinfunction "5_5") (pintype "passive"))
    )
    (net (code "16") (name "FPGA_5_35_N") (class "Default")
      (node (ref "U101") (pin "14") (pinfunction "14_5N_14") (pintype "bidirectional"))
      (node (ref "X722") (pin "4") (pinfunction "4_4") (pintype "passive"))
    )
    (net (code "17") (name "FPGA_5_35_P") (class "Default")
      (node (ref "U101") (pin "12") (pinfunction "12_5P_12") (pintype "bidirectional"))
      (node (ref "X722") (pin "3") (pinfunction "3_3") (pintype "passive"))
    )
    (net (code "18") (name "FPGA_7N35") (class "Default")
      (node (ref "R723") (pin "1") (pinfunction "1_1") (pintype "passive"))
      (node (ref "U101") (pin "4") (pinfunction "04_7N_4") (pintype "bidirectional"))
    )
    (net (code "19") (name "FPGA_9N35") (class "Default")
      (node (ref "R734") (pin "1") (pinfunction "1_1") (pintype "passive"))
      (node (ref "U101") (pin "17") (pinfunction "17_9N_17") (pintype "bidirectional"))
    )
    (net (code "20") (name "FPGA_10P35") (class "Default")
      (node (ref "R736") (pin "1") (pinfunction "1_1") (pintype "passive"))
      (node (ref "U101") (pin "22") (pinfunction "22_10P_22") (pintype "bidirectional"))
    )
    (net (code "21") (name "FPGA_11_16_N") (class "Default")
      (node (ref "U101") (pin "8") (pinfunction "08_11N_8") (pintype "bidirectional"))
      (node (ref "X721") (pin "8") (pinfunction "8_8") (pintype "passive"))
    )
    (net (code "22") (name "FPGA_11_16_P") (class "Default")
      (node (ref "U101") (pin "5") (pinfunction "05_11P_5") (pintype "bidirectional"))
      (node (ref "X721") (pin "7") (pinfunction "7_7") (pintype "passive"))
    )
    (net (code "23") (name "FPGA_12P16") (class "Default")
      (node (ref "R721") (pin "1") (pinfunction "1_1") (pintype "passive"))
      (node (ref "U101") (pin "3") (pinfunction "03_12P_3") (pintype "bidirectional"))
    )
    (net (code "24") (name "FPGA_12P34") (class "Default")
      (node (ref "R735") (pin "1") (pinfunction "1_1") (pintype "passive"))
      (node (ref "U101") (pin "36") (pinfunction "36_12P_36") (pintype "bidirectional"))
    )
    (net (code "25") (name "FPGA_13P_34") (class "Default")
      (node (ref "R722") (pin "1") (pinfunction "1_1") (pintype "passive"))
      (node (ref "U101") (pin "46") (pinfunction "46_13P_46") (pintype "bidirectional"))
    )
    (net (code "26") (name "FPGA_16_34_N") (class "Default")
      (node (ref "U101") (pin "39") (pinfunction "39_16N_39") (pintype "bidirectional"))
      (node (ref "X722") (pin "2") (pinfunction "2_2") (pintype "passive"))
    )
    (net (code "27") (name "FPGA_16_34_P") (class "Default")
      (node (ref "U101") (pin "41") (pinfunction "41_16P_41") (pintype "bidirectional"))
      (node (ref "X722") (pin "1") (pinfunction "1_1") (pintype "passive"))
    )
    (net (code "28") (name "FPGA_AD12") (class "Default")
      (node (ref "R733") (pin "1") (pinfunction "1_1") (pintype "passive"))
      (node (ref "U101") (pin "16") (pinfunction "16_AD12_16") (pintype "bidirectional"))
    )
    (net (code "29") (name "FPGA_FE09_DET") (class "Default")
      (node (ref "R521") (pin "2") (pinfunction "2_2") (pintype "passive"))
      (node (ref "U101") (pin "15") (pinfunction "15_AD4_15") (pintype "bidirectional"))
    )
    (net (code "30") (name "FPGA_I2C_SCL") (class "Default")
      (node (ref "R212") (pin "1") (pinfunction "1_1") (pintype "passive"))
      (node (ref "U101") (pin "26") (pinfunction "26_2P_26") (pintype "bidirectional"))
      (node (ref "U301") (pin "3") (pinfunction "SCL_3") (pintype "input"))
    )
    (net (code "31") (name "FPGA_I2C_SDA") (class "Default")
      (node (ref "R211") (pin "1") (pinfunction "1_1") (pintype "passive"))
      (node (ref "U101") (pin "27") (pinfunction "27_2N_27") (pintype "bidirectional"))
      (node (ref "U301") (pin "4") (pinfunction "SDA_4") (pintype "tri_state"))
    )
    (net (code "32") (name "FPGA_MISO") (class "Default")
      (node (ref "R114") (pin "1") (pinfunction "1_1") (pintype "passive"))
      (node (ref "U101") (pin "42") (pinfunction "42_9N_42") (pintype "bidirectional"))
    )
    (net (code "33") (name "FPGA_MOSI") (class "Default")
      (node (ref "R113") (pin "1") (pinfunction "1_1") (pintype "passive"))
      (node (ref "U101") (pin "43") (pinfunction "43_13N_43") (pintype "bidirectional"))
    )
    (net (code "34") (name "FPGA_SCLK") (class "Default")
      (node (ref "R111") (pin "1") (pinfunction "1_1") (pintype "passive"))
      (node (ref "U101") (pin "45") (pinfunction "45_19P_45") (pintype "bidirectional"))
    )
    (net (code "35") (name "FPGA_SELN") (class "Default")
      (node (ref "R112") (pin "1") (pinfunction "1_1") (pintype "passive"))
      (node (ref "U101") (pin "44") (pinfunction "44_9P_44") (pintype "bidirectional"))
    )
    (net (code "36") (name "FPGA_TRX_CLKO") (class "Default")
      (node (ref "C413") (pin "1") (pinfunction "1_1") (pintype "passive"))
      (node (ref "R413") (pin "1") (pinfunction "1_1") (pintype "passive"))
      (node (ref "U101") (pin "21") (pinfunction "21_10N_21") (pintype "bidirectional"))
    )
    (net (code "37") (name "FPGA_TRX_IRQ") (class "Default")
      (node (ref "R121") (pin "1") (pinfunction "1_1") (pintype "passive"))
      (node (ref "U101") (pin "40") (pinfunction "40_12N_40") (pintype "bidirectional"))
    )
    (net (code "38") (name "FPGA_TRX_RSTN") (class "Default")
      (node (ref "R131") (pin "2") (pinfunction "2_2") (pintype "passive"))
      (node (ref "U101") (pin "20") (pinfunction "20_9P_20") (pintype "bidirectional"))
    )
    (net (code "39") (name "GND") (class "Default")
      (node (ref "C221") (pin "2") (pinfunction "2_2") (pintype "passive"))
      (node (ref "C222") (pin "2") (pinfunction "2_2") (pintype "passive"))
      (node (ref "C311") (pin "2") (pinfunction "2_2") (pintype "passive"))
      (node (ref "C312") (pin "2") (pinfunction "2_2") (pintype "passive"))
      (node (ref "C321") (pin "2") (pinfunction "2_2") (pintype "passive"))
      (node (ref "C401") (pin "2") (pinfunction "2_2") (pintype "passive"))
      (node (ref "C411") (pin "2") (pinfunction "2_2") (pintype "passive"))
      (node (ref "C413") (pin "2") (pinfunction "2_2") (pintype "passive"))
      (node (ref "C511") (pin "2") (pinfunction "2_2") (pintype "passive"))
      (node (ref "C551") (pin "2") (pinfunction "2_2") (pintype "passive"))
      (node (ref "C552") (pin "2") (pinfunction "2_2") (pintype "passive"))
      (node (ref "C553") (pin "2") (pinfunction "2_2") (pintype "passive"))
      (node (ref "C591") (pin "2") (pinfunction "2_2") (pintype "passive"))
      (node (ref "C593") (pin "2") (pinfunction "2_2") (pintype "passive"))
      (node (ref "C595") (pin "2") (pinfunction "2_2") (pintype "passive"))
      (node (ref "C597") (pin "2") (pinfunction "2_2") (pintype "passive"))
      (node (ref "C601") (pin "2") (pinfunction "2_2") (pintype "passive"))
      (node (ref "C621") (pin "2") (pinfunction "2_2") (pintype "passive"))
      (node (ref "C711") (pin "1") (pinfunction "1_1") (pintype "passive"))
      (node (ref "D141") (pin "1") (pinfunction "BC_1") (pintype "passive"))
      (node (ref "D141") (pin "2") (pinfunction "GC_2") (pintype "passive"))
      (node (ref "D141") (pin "3") (pinfunction "RC_3") (pintype "passive"))
      (node (ref "H2311") (pin "B2,8") (pinfunction "MOUNT_B2,8") (pintype "passive"))
      (node (ref "H2321") (pin "B2,8") (pinfunction "MOUNT_B2,8") (pintype "passive"))
      (node (ref "H2331") (pin "B2,8") (pinfunction "MOUNT_B2,8") (pintype "passive"))
      (node (ref "H2341") (pin "B2,8") (pinfunction "MOUNT_B2,8") (pintype "passive"))
      (node (ref "L102") (pin "1") (pinfunction "1_1") (pintype "passive"))
      (node (ref "L401") (pin "1") (pinfunction "1_1") (pintype "passive"))
      (node (ref "L402") (pin "1") (pinfunction "1_1") (pintype "passive"))
      (node (ref "L421") (pin "1") (pinfunction "COM_1") (pintype "passive"))
      (node (ref "L422") (pin "2") (pinfunction "COM_2") (pintype "passive"))
      (node (ref "L422") (pin "5") (pinfunction "G_N_D_5") (pintype "passive"))
      (node (ref "R711") (pin "1") (pinfunction "1_1") (pintype "passive"))
      (node (ref "U301") (pin "2") (pinfunction "ADDR_2") (pintype "input"))
      (node (ref "U301") (pin "8") (pinfunction "GND_8") (pintype "passive"))
      (node (ref "U411") (pin "2") (pinfunction "GND_2") (pintype "power_in"))
      (node (ref "U511") (pin "2") (pinfunction "GND_2") (pintype "power_in"))
      (node (ref "U521") (pin "17") (pinfunction "VSS_17") (pintype "passive"))
      (node (ref "U521") (pin "4") (pinfunction "VSS_4") (pintype "passive"))
      (node (ref "U521") (pin "8") (pinfunction "VSS_8") (pintype "passive"))
      (node (ref "U581") (pin "1") (pinfunction "GROUND_1") (pintype "passive"))
      (node (ref "U581") (pin "3") (pinfunction "GROUND_3") (pintype "passive"))
      (node (ref "U581") (pin "4") (pinfunction "GROUND_4") (pintype "passive"))
      (node (ref "U581") (pin "6") (pinfunction "GROUND_6") (pintype "passive"))
      (node (ref "U611") (pin "10") (pinfunction "PGND_10") (pintype "passive"))
      (node (ref "U611") (pin "3") (pinfunction "VSS_3") (pintype "passive"))
      (node (ref "U611") (pin "6") (pinfunction "LBI_6") (pintype "input"))
      (node (ref "U611") (pin "7") (pinfunction "SYNC_7") (pintype "input"))
      (node (ref "X221") (pin "C") (pinfunction "C_C") (pintype "passive"))
      (node (ref "X221") (pin "D") (pinfunction "D_D") (pintype "passive"))
      (node (ref "X591") (pin "GND1") (pinfunction "GND_GND1") (pintype "bidirectional"))
      (node (ref "X591") (pin "GND2") (pinfunction "GND_GND2") (pintype "bidirectional"))
      (node (ref "X591") (pin "GND3") (pinfunction "GND_GND3") (pintype "bidirectional"))
      (node (ref "X591") (pin "GND4") (pinfunction "GND_GND4") (pintype "bidirectional"))
      (node (ref "X595") (pin "GND1") (pinfunction "GND_GND1") (pintype "bidirectional"))
      (node (ref "X595") (pin "GND2") (pinfunction "GND_GND2") (pintype "bidirectional"))
      (node (ref "X595") (pin "GND3") (pinfunction "GND_GND3") (pintype "bidirectional"))
      (node (ref "X595") (pin "GND4") (pinfunction "GND_GND4") (pintype "bidirectional"))
      (node (ref "X711") (pin "GND") (pinfunction "GND_GND") (pintype "passive"))
      (node (ref "X721") (pin "1") (pinfunction "1_1") (pintype "passive"))
      (node (ref "X723") (pin "8") (pinfunction "8_8") (pintype "passive"))
    )
    (net (code "40") (name "Net-(C403-Pad1)") (class "Default")
      (node (ref "C403") (pin "1") (pinfunction "1_1") (pintype "passive"))
      (node (ref "L403") (pin "2") (pinfunction "2_2") (pintype "passive"))
      (node (ref "U401") (pin "21") (pinfunction "DEVDD_21") (pintype "power_in"))
      (node (ref "U401") (pin "29") (pinfunction "DEVDD_29") (pintype "power_in"))
      (node (ref "U401") (pin "39") (pinfunction "DEVDD_39") (pintype "power_in"))
    )
    (net (code "41") (name "Net-(C403-Pad2)") (class "Default")
      (node (ref "C403") (pin "2") (pinfunction "2_2") (pintype "passive"))
      (node (ref "C406") (pin "1") (pinfunction "1_1") (pintype "passive"))
      (node (ref "L402") (pin "2") (pinfunction "2_2") (pintype "passive"))
      (node (ref "U401") (pin "20") (pinfunction "DVSS_20") (pintype "passive"))
      (node (ref "U401") (pin "23") (pinfunction "DVSS_23") (pintype "passive"))
      (node (ref "U401") (pin "24") (pinfunction "DVSS_24") (pintype "passive"))
      (node (ref "U401") (pin "32") (pinfunction "DVSS_32") (pintype "passive"))
      (node (ref "U401") (pin "38") (pinfunction "DVSS_38") (pintype "passive"))
    )
    (net (code "42") (name "Net-(C404-Pad1)") (class "Default")
      (node (ref "C404") (pin "1") (pinfunction "1_1") (pintype "passive"))
      (node (ref "L404") (pin "2") (pinfunction "2_2") (pintype "passive"))
      (node (ref "U401") (pin "15") (pinfunction "EVDD_15") (pintype "power_in"))
      (node (ref "U401") (pin "46") (pinfunction "EVDD_46") (pintype "power_in"))
    )
    (net (code "43") (name "Net-(C593-Pad1)") (class "Default")
      (node (ref "C593") (pin "1") (pinfunction "1_1") (pintype "passive"))
      (node (ref "L592") (pin "2") (pinfunction "2_2") (pintype "passive"))
      (node (ref "X591") (pin "ANT1") (pinfunction "SIGNAL_ANT1") (pintype "bidirectional"))
      (node (ref "X591") (pin "ANT2") (pinfunction "SIGNAL_ANT2") (pintype "bidirectional"))
      (node (ref "X591") (pin "ANT3") (pinfunction "SIGNAL_ANT3") (pintype "bidirectional"))
    )
    (net (code "44") (name "Net-(C597-Pad1)") (class "Default")
      (node (ref "C597") (pin "1") (pinfunction "1_1") (pintype "passive"))
      (node (ref "L596") (pin "2") (pinfunction "2_2") (pintype "passive"))
      (node (ref "X595") (pin "ANT1") (pinfunction "SIGNAL_ANT1") (pintype "bidirectional"))
      (node (ref "X595") (pin "ANT2") (pinfunction "SIGNAL_ANT2") (pintype "bidirectional"))
      (node (ref "X595") (pin "ANT3") (pinfunction "SIGNAL_ANT3") (pintype "bidirectional"))
    )
    (net (code "45") (name "Net-(C711-Pad2)") (class "Default")
      (node (ref "C711") (pin "2") (pinfunction "2_2") (pintype "passive"))
      (node (ref "R711") (pin "2") (pinfunction "2_2") (pintype "passive"))
      (node (ref "X711") (pin "JSHIELD") (pinfunction "SHIELD_JSHIELD") (pintype "passive"))
      (node (ref "X711") (pin "JSHIELD@2") (pinfunction "SHIELD_JSHIELD@2") (pintype "passive"))
      (node (ref "X711") (pin "JSHIELD@3") (pinfunction "SHIELD_JSHIELD@3") (pintype "passive"))
      (node (ref "X711") (pin "JSHIELD@4") (pinfunction "SHIELD_JSHIELD@4") (pintype "passive"))
      (node (ref "X711") (pin "JSHIELD@5") (pinfunction "SHIELD_JSHIELD@5") (pintype "passive"))
      (node (ref "X711") (pin "JSHIELD@6") (pinfunction "SHIELD_JSHIELD@6") (pintype "passive"))
    )
    (net (code "46") (name "Net-(D141-BA)") (class "Default")
      (node (ref "D141") (pin "6") (pinfunction "BA_6") (pintype "passive"))
      (node (ref "R143") (pin "1") (pinfunction "1_1") (pintype "passive"))
    )
    (net (code "47") (name "Net-(D141-GA)") (class "Default")
      (node (ref "D141") (pin "5") (pinfunction "GA_5") (pintype "passive"))
      (node (ref "R142") (pin "1") (pinfunction "1_1") (pintype "passive"))
    )
    (net (code "48") (name "Net-(D141-RA)") (class "Default")
      (node (ref "D141") (pin "4") (pinfunction "RA_4") (pintype "passive"))
      (node (ref "R141") (pin "1") (pinfunction "1_1") (pintype "passive"))
    )
    (net (code "49") (name "Net-(L421-B1)") (class "Default")
      (node (ref "L421") (pin "3") (pinfunction "B1_3") (pintype "passive"))
      (node (ref "U401") (pin "8") (pinfunction "RF09P_8") (pintype "passive"))
    )
    (net (code "50") (name "Net-(L421-B2)") (class "Default")
      (node (ref "L421") (pin "2") (pinfunction "B2_2") (pintype "passive"))
      (node (ref "U401") (pin "9") (pinfunction "RF09N_9") (pintype "passive"))
    )
    (net (code "51") (name "Net-(L422-B1)") (class "Default")
      (node (ref "L422") (pin "3") (pinfunction "B1_3") (pintype "passive"))
      (node (ref "U401") (pin "4") (pinfunction "RF24P_4") (pintype "passive"))
    )
    (net (code "52") (name "Net-(L422-B2)") (class "Default")
      (node (ref "L422") (pin "4") (pinfunction "B2_4") (pintype "passive"))
      (node (ref "U401") (pin "5") (pinfunction "RF24N_5") (pintype "passive"))
    )
    (net (code "53") (name "Net-(R721-Pad2)") (class "Default")
      (node (ref "R721") (pin "2") (pinfunction "2_2") (pintype "passive"))
      (node (ref "X721") (pin "2") (pinfunction "2_2") (pintype "passive"))
    )
    (net (code "54") (name "Net-(R722-Pad2)") (class "Default")
      (node (ref "R722") (pin "2") (pinfunction "2_2") (pintype "passive"))
      (node (ref "X721") (pin "3") (pinfunction "3_3") (pintype "passive"))
    )
    (net (code "55") (name "Net-(R723-Pad2)") (class "Default")
      (node (ref "R723") (pin "2") (pinfunction "2_2") (pintype "passive"))
      (node (ref "X721") (pin "4") (pinfunction "4_4") (pintype "passive"))
    )
    (net (code "56") (name "Net-(R724-Pad2)") (class "Default")
      (node (ref "R724") (pin "2") (pinfunction "2_2") (pintype "passive"))
      (node (ref "X721") (pin "5") (pinfunction "5_5") (pintype "passive"))
    )
    (net (code "57") (name "Net-(R733-Pad2)") (class "Default")
      (node (ref "R733") (pin "2") (pinfunction "2_2") (pintype "passive"))
      (node (ref "X723") (pin "3") (pinfunction "3_3") (pintype "passive"))
    )
    (net (code "58") (name "Net-(R734-Pad2)") (class "Default")
      (node (ref "R734") (pin "2") (pinfunction "2_2") (pintype "passive"))
      (node (ref "X723") (pin "4") (pinfunction "4_4") (pintype "passive"))
    )
    (net (code "59") (name "Net-(R735-Pad2)") (class "Default")
      (node (ref "R735") (pin "2") (pinfunction "2_2") (pintype "passive"))
      (node (ref "X723") (pin "5") (pinfunction "5_5") (pintype "passive"))
    )
    (net (code "60") (name "Net-(R736-Pad2)") (class "Default")
      (node (ref "R736") (pin "2") (pinfunction "2_2") (pintype "passive"))
      (node (ref "X723") (pin "6") (pinfunction "6_6") (pintype "passive"))
    )
    (net (code "61") (name "Net-(U101-07_6N)") (class "Default")
      (node (ref "R151") (pin "2") (pinfunction "2_2") (pintype "passive"))
      (node (ref "U101") (pin "7") (pinfunction "07_6N_7") (pintype "bidirectional"))
    )
    (net (code "62") (name "Net-(U101-09_6P)") (class "Default")
      (node (ref "R141") (pin "2") (pinfunction "2_2") (pintype "passive"))
      (node (ref "U101") (pin "9") (pinfunction "09_6P_9") (pintype "bidirectional"))
    )
    (net (code "63") (name "Net-(U101-10_7P)") (class "Default")
      (node (ref "R142") (pin "2") (pinfunction "2_2") (pintype "passive"))
      (node (ref "U101") (pin "10") (pinfunction "10_7P_10") (pintype "bidirectional"))
    )
    (net (code "64") (name "Net-(U101-11_3N)") (class "Default")
      (node (ref "R143") (pin "2") (pinfunction "2_2") (pintype "passive"))
      (node (ref "U101") (pin "11") (pinfunction "11_3N_11") (pintype "bidirectional"))
    )
    (net (code "65") (name "Net-(U101-13_6N)") (class "Default")
      (node (ref "R152") (pin "2") (pinfunction "2_2") (pintype "passive"))
      (node (ref "U101") (pin "13") (pinfunction "13_6N_13") (pintype "bidirectional"))
    )
    (net (code "66") (name "Net-(U401-AVDD0)") (class "Default")
      (node (ref "C407") (pin "2") (pinfunction "2_2") (pintype "passive"))
      (node (ref "U401") (pin "14") (pinfunction "AVDD0_14") (pintype "passive"))
    )
    (net (code "67") (name "Net-(U401-AVDD1)") (class "Default")
      (node (ref "C408") (pin "2") (pinfunction "2_2") (pintype "passive"))
      (node (ref "U401") (pin "47") (pinfunction "AVDD1_47") (pintype "passive"))
    )
    (net (code "68") (name "Net-(U401-CLKO)") (class "Default")
      (node (ref "R413") (pin "2") (pinfunction "2_2") (pintype "passive"))
      (node (ref "U401") (pin "22") (pinfunction "CLKO_22") (pintype "output"))
    )
    (net (code "69") (name "Net-(U401-DVDD)") (class "Default")
      (node (ref "C406") (pin "2") (pinfunction "2_2") (pintype "passive"))
      (node (ref "U401") (pin "37") (pinfunction "DVDD_37") (pintype "passive"))
    )
    (net (code "70") (name "Net-(U401-TCXO)") (class "Default")
      (node (ref "C412") (pin "2") (pinfunction "2_2") (pintype "passive"))
      (node (ref "U401") (pin "17") (pinfunction "TCXO_17") (pintype "input"))
    )
    (net (code "71") (name "Net-(U401-XTAL2)") (class "Default")
      (node (ref "C404") (pin "2") (pinfunction "2_2") (pintype "passive"))
      (node (ref "C407") (pin "1") (pinfunction "1_1") (pintype "passive"))
      (node (ref "C408") (pin "1") (pinfunction "1_1") (pintype "passive"))
      (node (ref "L401") (pin "2") (pinfunction "2_2") (pintype "passive"))
      (node (ref "U401") (pin "10") (pinfunction "AVSS_10") (pintype "passive"))
      (node (ref "U401") (pin "16") (pinfunction "AVSS_16") (pintype "passive"))
      (node (ref "U401") (pin "18") (pinfunction "XTAL2_18") (pintype "passive"))
      (node (ref "U401") (pin "19") (pinfunction "AVSS_19") (pintype "passive"))
      (node (ref "U401") (pin "3") (pinfunction "AVSS_3") (pintype "passive"))
      (node (ref "U401") (pin "45") (pinfunction "AVSS_45") (pintype "passive"))
      (node (ref "U401") (pin "48") (pinfunction "AVSS_48") (pintype "passive"))
      (node (ref "U401") (pin "49") (pinfunction "AVSS_49") (pintype "passive"))
      (node (ref "U401") (pin "6") (pinfunction "AVSS_6") (pintype "passive"))
      (node (ref "U401") (pin "7") (pinfunction "AVSS_7") (pintype "passive"))
    )
    (net (code "72") (name "Net-(U411-OUT)") (class "Default")
      (node (ref "C412") (pin "1") (pinfunction "1_1") (pintype "passive"))
      (node (ref "U411") (pin "3") (pinfunction "OUT_3") (pintype "output"))
    )
    (net (code "73") (name "Net-(U511-RF1)") (class "Default")
      (node (ref "C531") (pin "2") (pinfunction "2_2") (pintype "passive"))
      (node (ref "U511") (pin "1") (pinfunction "RF1_1") (pintype "passive"))
    )
    (net (code "74") (name "Net-(U511-RF2)") (class "Default")
      (node (ref "C532") (pin "2") (pinfunction "2_2") (pintype "passive"))
      (node (ref "U511") (pin "3") (pinfunction "RF2_3") (pintype "passive"))
    )
    (net (code "75") (name "Net-(U511-RFC)") (class "Default")
      (node (ref "C521") (pin "1") (pinfunction "1_1") (pintype "passive"))
      (node (ref "U511") (pin "5") (pinfunction "RFC_5") (pintype "passive"))
    )
    (net (code "76") (name "Net-(U521-IND)") (class "Default")
      (node (ref "L521") (pin "1") (pinfunction "1_1") (pintype "passive"))
      (node (ref "U521") (pin "10") (pinfunction "IND_10") (pintype "passive"))
    )
    (net (code "77") (name "Net-(U581-OUT)") (class "Default")
      (node (ref "C591") (pin "1") (pinfunction "1_1") (pintype "passive"))
      (node (ref "L592") (pin "1") (pinfunction "1_1") (pintype "passive"))
      (node (ref "U581") (pin "5") (pinfunction "OUT_5") (pintype "passive"))
    )
    (net (code "78") (name "Net-(U611-SW)") (class "Default")
      (node (ref "L611") (pin "2") (pinfunction "2_2") (pintype "passive"))
      (node (ref "U611") (pin "9") (pinfunction "SW_9") (pintype "passive"))
    )
    (net (code "79") (name "Net-(X711-J_VUSB)") (class "Default")
      (node (ref "PF711") (pin "2") (pinfunction "2_2") (pintype "passive"))
      (node (ref "X711") (pin "VBUS") (pinfunction "J_VUSB_VBUS") (pintype "power_in"))
    )
    (net (code "80") (name "ROT_I_R") (class "Default")
      (node (ref "C221") (pin "1") (pinfunction "1_1") (pintype "passive"))
      (node (ref "R151") (pin "1") (pinfunction "1_1") (pintype "passive"))
      (node (ref "X221") (pin "A") (pinfunction "A_A") (pintype "passive"))
    )
    (net (code "81") (name "ROT_Q_R") (class "Default")
      (node (ref "C222") (pin "1") (pinfunction "1_1") (pintype "passive"))
      (node (ref "R152") (pin "1") (pinfunction "1_1") (pintype "passive"))
      (node (ref "X221") (pin "B") (pinfunction "B_B") (pintype "passive"))
    )
    (net (code "82") (name "TRX_FEA09") (class "Default")
      (node (ref "U401") (pin "11") (pinfunction "FEA09_11") (pintype "output"))
      (node (ref "U511") (pin "4") (pinfunction "CTRL_4") (pintype "input"))
      (node (ref "U521") (pin "2") (pinfunction "TXEN_2") (pintype "input"))
    )
    (net (code "83") (name "TRX_FEA24") (class "Default")
      (node (ref "U401") (pin "1") (pinfunction "FEA24_1") (pintype "output"))
    )
    (net (code "84") (name "TRX_FEB09") (class "Default")
      (node (ref "U401") (pin "12") (pinfunction "FEB09_12") (pintype "output"))
      (node (ref "U521") (pin "1") (pinfunction "RXEN_1") (pintype "input"))
    )
    (net (code "85") (name "TRX_FEB24") (class "Default")
      (node (ref "U401") (pin "2") (pinfunction "FEB24_2") (pintype "output"))
    )
    (net (code "86") (name "TRX_IRQ") (class "Default")
      (node (ref "R121") (pin "2") (pinfunction "2_2") (pintype "passive"))
      (node (ref "U401") (pin "40") (pinfunction "IRQ_40") (pintype "output"))
    )
    (net (code "87") (name "TRX_MISO") (class "Default")
      (node (ref "R114") (pin "2") (pinfunction "2_2") (pintype "passive"))
      (node (ref "U401") (pin "44") (pinfunction "MISO_44") (pintype "output"))
    )
    (net (code "88") (name "TRX_MOSI") (class "Default")
      (node (ref "R113") (pin "2") (pinfunction "2_2") (pintype "passive"))
      (node (ref "U401") (pin "43") (pinfunction "MOSI_43") (pintype "input"))
    )
    (net (code "89") (name "TRX_RF09") (class "Default")
      (node (ref "C521") (pin "2") (pinfunction "2_2") (pintype "passive"))
      (node (ref "L421") (pin "4") (pinfunction "UB_4") (pintype "passive"))
    )
    (net (code "90") (name "TRX_RF24") (class "Default")
      (node (ref "C595") (pin "1") (pinfunction "1_1") (pintype "passive"))
      (node (ref "L422") (pin "1") (pinfunction "UB_1") (pintype "passive"))
      (node (ref "L596") (pin "1") (pinfunction "1_1") (pintype "passive"))
    )
    (net (code "91") (name "TRX_RSTN") (class "Default")
      (node (ref "R131") (pin "1") (pinfunction "1_1") (pintype "passive"))
      (node (ref "U401") (pin "13") (pinfunction "RSTN_13") (pintype "input"))
    )
    (net (code "92") (name "TRX_RXCLK_N") (class "Default")
      (node (ref "U101") (pin "48") (pinfunction "48_14N_48") (pintype "bidirectional"))
      (node (ref "U401") (pin "33") (pinfunction "RXCLKN_33") (pintype "output"))
    )
    (net (code "93") (name "TRX_RXCLK_P") (class "Default")
      (node (ref "U101") (pin "47") (pinfunction "47_14P_47") (pintype "bidirectional"))
      (node (ref "U401") (pin "34") (pinfunction "RXCLKP_34") (pintype "output"))
    )
    (net (code "94") (name "TRX_RXD09_N") (class "Default")
      (node (ref "U101") (pin "37") (pinfunction "37_11N_37") (pintype "bidirectional"))
      (node (ref "U401") (pin "30") (pinfunction "RXD09N_30") (pintype "output"))
    )
    (net (code "95") (name "TRX_RXD09_P") (class "Default")
      (node (ref "U101") (pin "38") (pinfunction "38_11P_38") (pintype "bidirectional"))
      (node (ref "U401") (pin "31") (pinfunction "RXD09P_31") (pintype "output"))
    )
    (net (code "96") (name "TRX_RXD24_N") (class "Default")
      (node (ref "U101") (pin "1") (pinfunction "01_8N_1") (pintype "bidirectional"))
      (node (ref "U401") (pin "35") (pinfunction "RXD24N_35") (pintype "output"))
    )
    (net (code "97") (name "TRX_RXD24_P") (class "Default")
      (node (ref "U101") (pin "2") (pinfunction "02_8P_2") (pintype "bidirectional"))
      (node (ref "U401") (pin "36") (pinfunction "RXD24P_36") (pintype "output"))
    )
    (net (code "98") (name "TRX_SCLK") (class "Default")
      (node (ref "R111") (pin "2") (pinfunction "2_2") (pintype "passive"))
      (node (ref "U401") (pin "41") (pinfunction "SCLK_41") (pintype "input"))
    )
    (net (code "99") (name "TRX_SELN") (class "Default")
      (node (ref "R112") (pin "2") (pinfunction "2_2") (pintype "passive"))
      (node (ref "U401") (pin "42") (pinfunction "SELN_42") (pintype "input"))
    )
    (net (code "100") (name "TRX_TXCLK_N") (class "Default")
      (node (ref "U101") (pin "19") (pinfunction "19_12N_19") (pintype "bidirectional"))
      (node (ref "U401") (pin "25") (pinfunction "TXCLKN_25") (pintype "input"))
    )
    (net (code "101") (name "TRX_TXCLK_P") (class "Default")
      (node (ref "U101") (pin "18") (pinfunction "18_12P_18") (pintype "bidirectional"))
      (node (ref "U401") (pin "26") (pinfunction "TXCLKP_26") (pintype "input"))
    )
    (net (code "102") (name "TRX_TXD_N") (class "Default")
      (node (ref "U101") (pin "34") (pinfunction "34_6N_34") (pintype "bidirectional"))
      (node (ref "U401") (pin "27") (pinfunction "TXDN_27") (pintype "input"))
    )
    (net (code "103") (name "TRX_TXD_P") (class "Default")
      (node (ref "U101") (pin "35") (pinfunction "35_6P_35") (pintype "bidirectional"))
      (node (ref "U401") (pin "28") (pinfunction "TXDP_28") (pintype "input"))
    )
    (net (code "104") (name "VCCA") (class "Default")
      (node (ref "C101") (pin "2") (pinfunction "2_2") (pintype "passive"))
      (node (ref "L101") (pin "2") (pinfunction "2_2") (pintype "passive"))
      (node (ref "U101") (pin "24") (pinfunction "24_VU_24") (pintype "power_in"))
    )
    (net (code "105") (name "VCTCXO_VC") (class "Default")
      (node (ref "C321") (pin "1") (pinfunction "1_1") (pintype "passive"))
      (node (ref "R321") (pin "2") (pinfunction "2_2") (pintype "passive"))
      (node (ref "U411") (pin "1") (pinfunction "VC_1") (pintype "input"))
    )
    (net (code "106") (name "VSSA") (class "Default")
      (node (ref "C101") (pin "1") (pinfunction "1_1") (pintype "passive"))
      (node (ref "L102") (pin "2") (pinfunction "2_2") (pintype "passive"))
      (node (ref "U101") (pin "25") (pinfunction "25_GND_25") (pintype "passive"))
    )
    (net (code "107") (name "unconnected-(U521-DC-Pad6)") (class "Default")
      (node (ref "U521") (pin "6") (pinfunction "DC_6") (pintype "no_connect"))
    )
    (net (code "108") (name "unconnected-(U521-DC-Pad11)") (class "Default")
      (node (ref "U521") (pin "11") (pinfunction "DC_11") (pintype "no_connect"))
    )
    (net (code "109") (name "unconnected-(U521-DC-Pad12)") (class "Default")
      (node (ref "U521") (pin "12") (pinfunction "DC_12") (pintype "no_connect"))
    )
    (net (code "110") (name "unconnected-(U611-LBO-Pad2)") (class "Default")
      (node (ref "U611") (pin "2") (pinfunction "LBO_2") (pintype "output"))
    )
    (net (code "111") (name "unconnected-(U611-PG-Pad4)") (class "Default")
      (node (ref "U611") (pin "4") (pinfunction "PG_4") (pintype "output"))
    )
    (net (code "112") (name "unconnected-(X221-PadE)") (class "Default")
      (node (ref "X221") (pin "E") (pinfunction "E_E") (pintype "passive"))
    )
    (net (code "113") (name "unconnected-(X711-J_D+-PadD+)") (class "Default")
      (node (ref "X711") (pin "D+") (pinfunction "J_D+_D+") (pintype "bidirectional"))
    )
    (net (code "114") (name "unconnected-(X711-J_D--PadD-)") (class "Default")
      (node (ref "X711") (pin "D-") (pinfunction "J_D-_D-") (pintype "bidirectional"))
    )
    (net (code "115") (name "unconnected-(X711-J_ID-PadID)") (class "Default")
      (node (ref "X711") (pin "ID") (pinfunction "J_ID_ID") (pintype "bidirectional"))
    )
  )
)
